# FPGA.net
KiCad netlist of a schematic drawn in Altium Designer
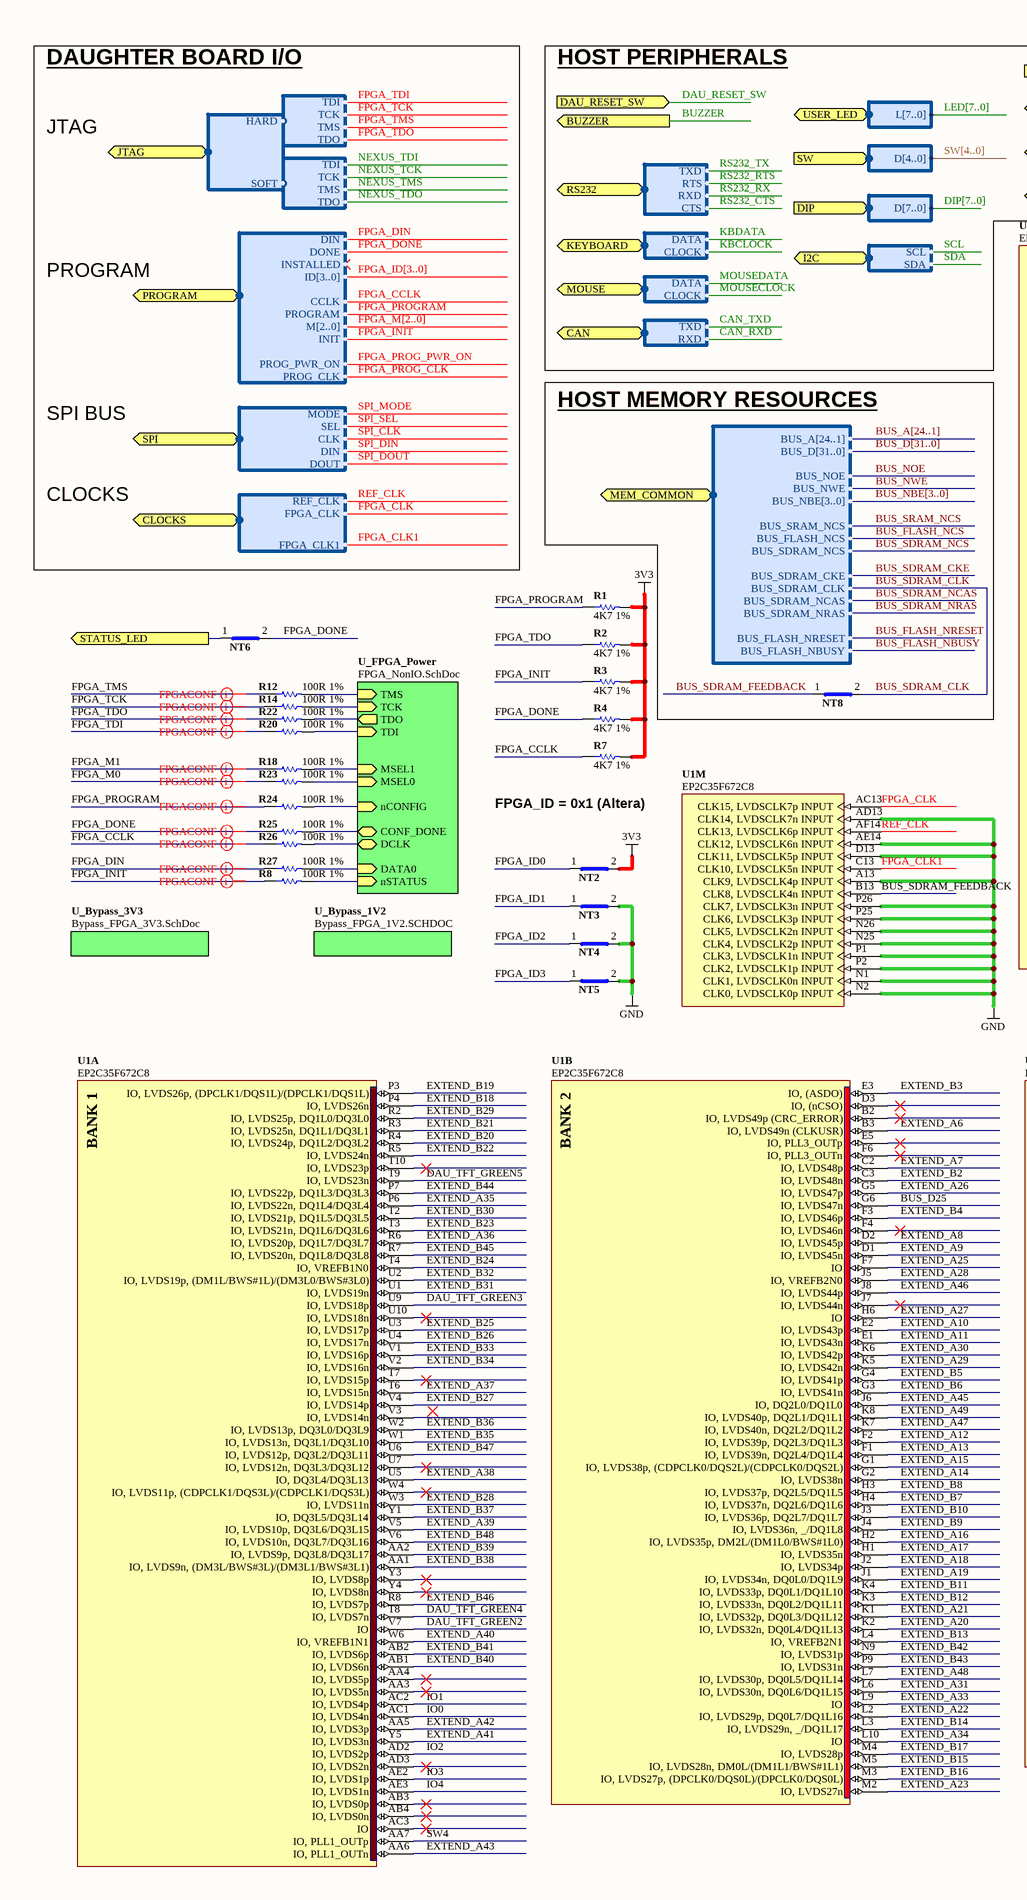
[diagram p0: FPGA.SCHDOC, left]
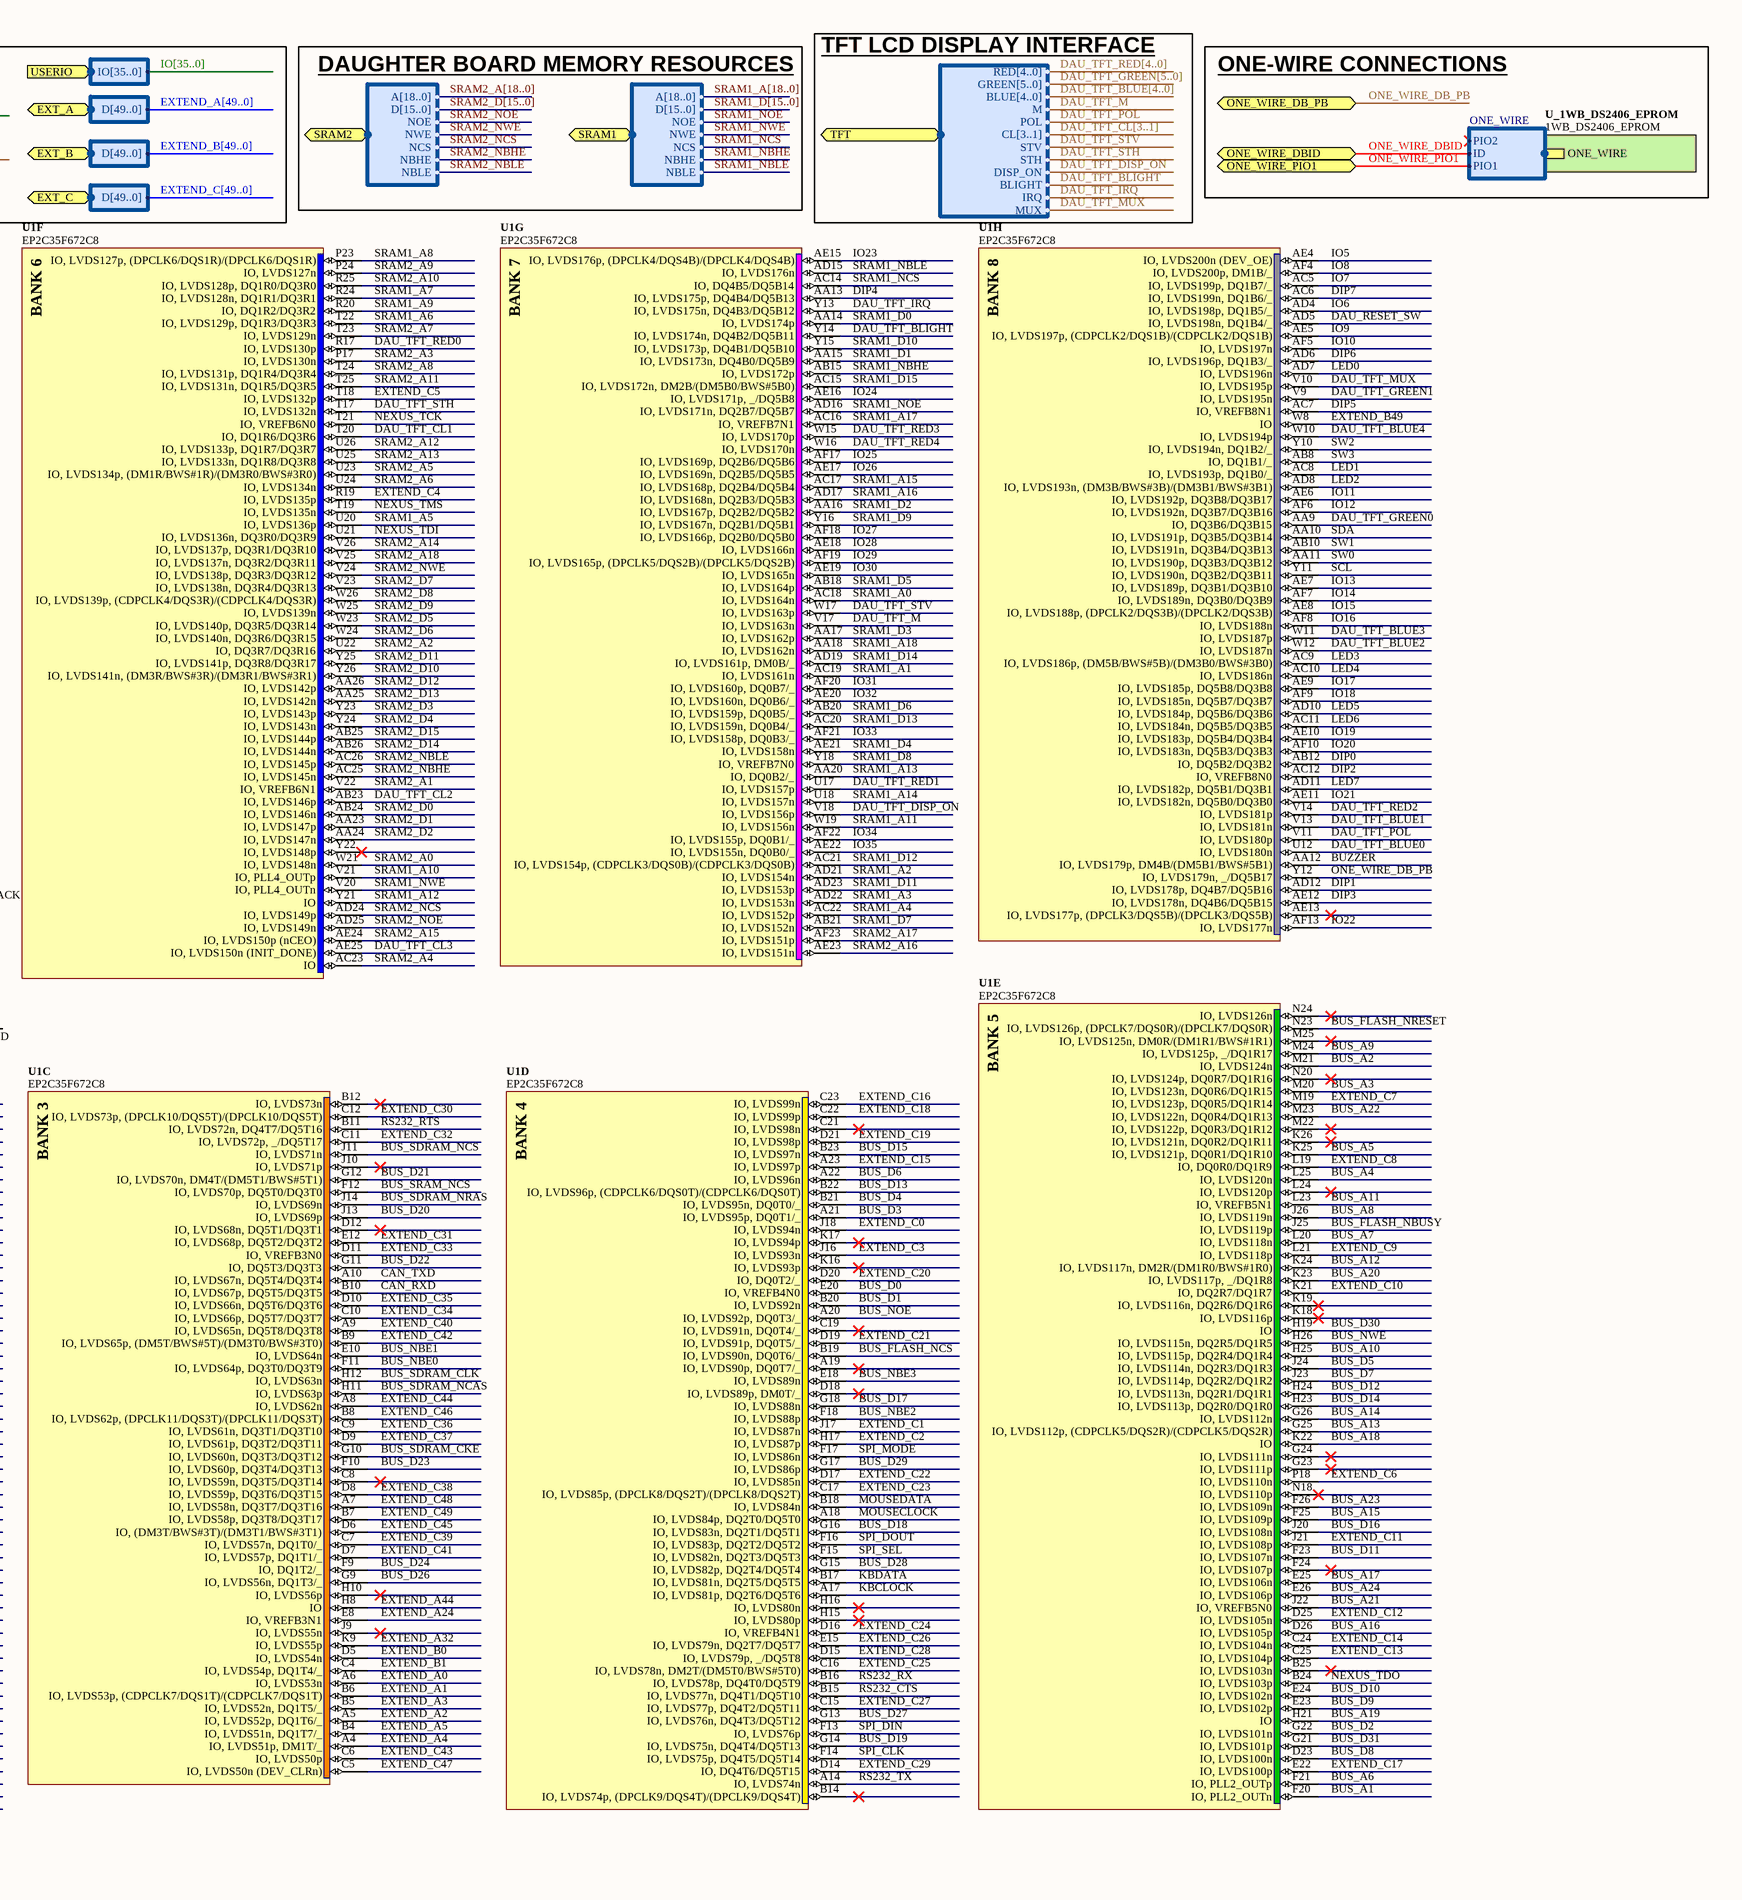
[diagram p1: FPGA.SCHDOC, right]

(export (version "E")
  (design (tool "Eeschema 10.0.6"))
  (components
    (comp (ref "NT2")
      (value "Net Tie SMT2")
      (footprint "NETTIE-SMT2-8X8")
      (description "Net-Tie, Surface Mount, 2 x 0.4mm x 0.2mm SMT Pads - For 0.2mm Track")
      (libsource (lib "AltiumDesignLibrary") (part "NETTIE-SMT2"))
    )
    (comp (ref "NT3")
      (value "Net Tie SMT2")
      (footprint "NETTIE-SMT2-8X8")
      (description "Net-Tie, Surface Mount, 2 x 0.4mm x 0.2mm SMT Pads - For 0.2mm Track")
      (libsource (lib "AltiumDesignLibrary") (part "NETTIE-SMT2"))
    )
    (comp (ref "NT4")
      (value "Net Tie SMT2")
      (footprint "NETTIE-SMT2-8X8")
      (description "Net-Tie, Surface Mount, 2 x 0.4mm x 0.2mm SMT Pads - For 0.2mm Track")
      (libsource (lib "AltiumDesignLibrary") (part "NETTIE-SMT2"))
    )
    (comp (ref "NT5")
      (value "Net Tie SMT2")
      (footprint "NETTIE-SMT2-8X8")
      (description "Net-Tie, Surface Mount, 2 x 0.4mm x 0.2mm SMT Pads - For 0.2mm Track")
      (libsource (lib "AltiumDesignLibrary") (part "NETTIE-SMT2"))
    )
    (comp (ref "NT6")
      (value "Net Tie SMT2")
      (footprint "NETTIE-SMT2-8X8")
      (description "Net-Tie, Surface Mount, 2 x 0.4mm x 0.2mm SMT Pads - For 0.2mm Track")
      (libsource (lib "AltiumDesignLibrary") (part "NETTIE-SMT2"))
    )
    (comp (ref "NT8")
      (value "Net Tie SMT2")
      (footprint "NETTIE-SMT2-8X8")
      (description "Net-Tie, Surface Mount, 2 x 0.4mm x 0.2mm SMT Pads - For 0.2mm Track")
      (libsource (lib "AltiumDesignLibrary") (part "NETTIE-SMT2"))
    )
    (comp (ref "R1")
      (value "4K7 1%")
      (footprint "RESC1005-STAR")
      (description "Resistor, 4K7 1% 0402 (1005)")
      (fields (field (name "TOLERANCE") "1 %"))
      (libsource (lib "AltiumDesignLibrary") (part "RES"))
    )
    (comp (ref "R2")
      (value "4K7 1%")
      (footprint "RESC1005-STAR")
      (description "Resistor, 4K7 1% 0402 (1005)")
      (fields (field (name "TOLERANCE") "1 %"))
      (libsource (lib "AltiumDesignLibrary") (part "RES"))
    )
    (comp (ref "R3")
      (value "4K7 1%")
      (footprint "RESC1005-STAR")
      (description "Resistor, 4K7 1% 0402 (1005)")
      (fields (field (name "TOLERANCE") "1 %"))
      (libsource (lib "AltiumDesignLibrary") (part "RES"))
    )
    (comp (ref "R4")
      (value "4K7 1%")
      (footprint "RESC1005-STAR")
      (description "Resistor, 4K7 1% 0402 (1005)")
      (fields (field (name "TOLERANCE") "1 %"))
      (libsource (lib "AltiumDesignLibrary") (part "RES"))
    )
    (comp (ref "R7")
      (value "4K7 1%")
      (footprint "RESC1005-STAR")
      (description "Resistor, 4K7 1% 0402 (1005)")
      (fields (field (name "TOLERANCE") "1 %"))
      (libsource (lib "AltiumDesignLibrary") (part "RES"))
    )
    (comp (ref "R8")
      (value "100R 1%")
      (footprint "RESC1005-STAR")
      (description "Resistor, 100R 1% 0402 (1005)")
      (fields (field (name "TOLERANCE") "1 %"))
      (libsource (lib "AltiumDesignLibrary") (part "RES"))
    )
    (comp (ref "R12")
      (value "100R 1%")
      (footprint "RESC1005-STAR")
      (description "Resistor, 100R 1% 0402 (1005)")
      (fields (field (name "TOLERANCE") "1 %"))
      (libsource (lib "AltiumDesignLibrary") (part "RES"))
    )
    (comp (ref "R14")
      (value "100R 1%")
      (footprint "RESC1005-STAR")
      (description "Resistor, 100R 1% 0402 (1005)")
      (fields (field (name "TOLERANCE") "1 %"))
      (libsource (lib "AltiumDesignLibrary") (part "RES"))
    )
    (comp (ref "R18")
      (value "100R 1%")
      (footprint "RESC1005-STAR")
      (description "Resistor, 100R 1% 0402 (1005)")
      (fields (field (name "TOLERANCE") "1 %"))
      (libsource (lib "AltiumDesignLibrary") (part "RES"))
    )
    (comp (ref "R20")
      (value "100R 1%")
      (footprint "RESC1005-STAR")
      (description "Resistor, 100R 1% 0402 (1005)")
      (fields (field (name "TOLERANCE") "1 %"))
      (libsource (lib "AltiumDesignLibrary") (part "RES"))
    )
    (comp (ref "R22")
      (value "100R 1%")
      (footprint "RESC1005-STAR")
      (description "Resistor, 100R 1% 0402 (1005)")
      (fields (field (name "TOLERANCE") "1 %"))
      (libsource (lib "AltiumDesignLibrary") (part "RES"))
    )
    (comp (ref "R23")
      (value "100R 1%")
      (footprint "RESC1005-STAR")
      (description "Resistor, 100R 1% 0402 (1005)")
      (fields (field (name "TOLERANCE") "1 %"))
      (libsource (lib "AltiumDesignLibrary") (part "RES"))
    )
    (comp (ref "R24")
      (value "100R 1%")
      (footprint "RESC1005-STAR")
      (description "Resistor, 100R 1% 0402 (1005)")
      (fields (field (name "TOLERANCE") "1 %"))
      (libsource (lib "AltiumDesignLibrary") (part "RES"))
    )
    (comp (ref "R25")
      (value "100R 1%")
      (footprint "RESC1005-STAR")
      (description "Resistor, 100R 1% 0402 (1005)")
      (fields (field (name "TOLERANCE") "1 %"))
      (libsource (lib "AltiumDesignLibrary") (part "RES"))
    )
    (comp (ref "R26")
      (value "100R 1%")
      (footprint "RESC1005-STAR")
      (description "Resistor, 100R 1% 0402 (1005)")
      (fields (field (name "TOLERANCE") "1 %"))
      (libsource (lib "AltiumDesignLibrary") (part "RES"))
    )
    (comp (ref "R27")
      (value "100R 1%")
      (footprint "RESC1005-STAR")
      (description "Resistor, 100R 1% 0402 (1005)")
      (fields (field (name "TOLERANCE") "1 %"))
      (libsource (lib "AltiumDesignLibrary") (part "RES"))
    )
    (comp (ref "U1")
      (value "EP2C35F672C8")
      (footprint "BGA100P26X26-672")
      (description "FPGA, Altera Cyclone2-35 F672")
      (libsource (lib "AltiumDesignLibrary") (part "EP2C35F672C8"))
    )
  )
  (nets
    (net (code "20") (name "/BUS_A1") (class "Default")
      (node (ref "U1") (pin "F20") (pinfunction "IO,_PLL2_OUTn_F20") (pintype "bidirectional"))
    )
    (net (code "21") (name "/BUS_A2") (class "Default")
      (node (ref "U1") (pin "M21") (pinfunction "IO,_LVDS124n_M21") (pintype "bidirectional"))
    )
    (net (code "22") (name "/BUS_A3") (class "Default")
      (node (ref "U1") (pin "M20") (pinfunction "IO,_LVDS123n,_DQ0R6/DQ1R15_M20") (pintype "bidirectional"))
    )
    (net (code "23") (name "/BUS_A4") (class "Default")
      (node (ref "U1") (pin "L25") (pinfunction "IO,_LVDS120n_L25") (pintype "bidirectional"))
    )
    (net (code "24") (name "/BUS_A5") (class "Default")
      (node (ref "U1") (pin "K25") (pinfunction "IO,_LVDS121p,_DQ0R1/DQ1R10_K25") (pintype "bidirectional"))
    )
    (net (code "25") (name "/BUS_A6") (class "Default")
      (node (ref "U1") (pin "F21") (pinfunction "IO,_PLL2_OUTp_F21") (pintype "bidirectional"))
    )
    (net (code "26") (name "/BUS_A7") (class "Default")
      (node (ref "U1") (pin "L20") (pinfunction "IO,_LVDS118n_L20") (pintype "bidirectional"))
    )
    (net (code "27") (name "/BUS_A8") (class "Default")
      (node (ref "U1") (pin "J26") (pinfunction "IO,_LVDS119n_J26") (pintype "bidirectional"))
    )
    (net (code "28") (name "/BUS_A9") (class "Default")
      (node (ref "U1") (pin "M24") (pinfunction "IO,_LVDS125p,__/DQ1R17_M24") (pintype "bidirectional"))
    )
    (net (code "29") (name "/BUS_A10") (class "Default")
      (node (ref "U1") (pin "H25") (pinfunction "IO,_LVDS115p,_DQ2R4/DQ1R4_H25") (pintype "bidirectional"))
    )
    (net (code "30") (name "/BUS_A11") (class "Default")
      (node (ref "U1") (pin "L23") (pinfunction "IO,_VREFB5N1_L23") (pintype "bidirectional"))
    )
    (net (code "31") (name "/BUS_A12") (class "Default")
      (node (ref "U1") (pin "K24") (pinfunction "IO,_LVDS117n,_DM2R/(DM1R0/BWS#1R0)_K24") (pintype "bidirectional"))
    )
    (net (code "32") (name "/BUS_A13") (class "Default")
      (node (ref "U1") (pin "G25") (pinfunction "IO,_LVDS112p,_(CDPCLK5/DQS2R)/(CDPCLK5/DQS2R)_G25") (pintype "bidirectional"))
    )
    (net (code "33") (name "/BUS_A14") (class "Default")
      (node (ref "U1") (pin "G26") (pinfunction "IO,_LVDS112n_G26") (pintype "bidirectional"))
    )
    (net (code "34") (name "/BUS_A15") (class "Default")
      (node (ref "U1") (pin "F25") (pinfunction "IO,_LVDS109p_F25") (pintype "bidirectional"))
    )
    (net (code "35") (name "/BUS_A16") (class "Default")
      (node (ref "U1") (pin "D26") (pinfunction "IO,_LVDS105p_D26") (pintype "bidirectional"))
    )
    (net (code "36") (name "/BUS_A17") (class "Default")
      (node (ref "U1") (pin "E25") (pinfunction "IO,_LVDS106n_E25") (pintype "bidirectional"))
    )
    (net (code "37") (name "/BUS_A18") (class "Default")
      (node (ref "U1") (pin "K22") (pinfunction "IO_K22") (pintype "bidirectional"))
    )
    (net (code "38") (name "/BUS_A19") (class "Default")
      (node (ref "U1") (pin "H21") (pinfunction "IO_H21") (pintype "bidirectional"))
    )
    (net (code "39") (name "/BUS_A20") (class "Default")
      (node (ref "U1") (pin "K23") (pinfunction "IO,_LVDS117p,__/DQ1R8_K23") (pintype "bidirectional"))
    )
    (net (code "40") (name "/BUS_A21") (class "Default")
      (node (ref "U1") (pin "J22") (pinfunction "IO,_VREFB5N0_J22") (pintype "bidirectional"))
    )
    (net (code "41") (name "/BUS_A22") (class "Default")
      (node (ref "U1") (pin "M23") (pinfunction "IO,_LVDS122n,_DQ0R4/DQ1R13_M23") (pintype "bidirectional"))
    )
    (net (code "42") (name "/BUS_A23") (class "Default")
      (node (ref "U1") (pin "F26") (pinfunction "IO,_LVDS109n_F26") (pintype "bidirectional"))
    )
    (net (code "43") (name "/BUS_A24") (class "Default")
      (node (ref "U1") (pin "E26") (pinfunction "IO,_LVDS106p_E26") (pintype "bidirectional"))
    )
    (net (code "44") (name "/BUS_D0") (class "Default")
      (node (ref "U1") (pin "E20") (pinfunction "IO,_VREFB4N0_E20") (pintype "bidirectional"))
    )
    (net (code "45") (name "/BUS_D1") (class "Default")
      (node (ref "U1") (pin "B20") (pinfunction "IO,_LVDS92n_B20") (pintype "bidirectional"))
    )
    (net (code "46") (name "/BUS_D2") (class "Default")
      (node (ref "U1") (pin "G22") (pinfunction "IO,_LVDS101n_G22") (pintype "bidirectional"))
    )
    (net (code "47") (name "/BUS_D3") (class "Default")
      (node (ref "U1") (pin "A21") (pinfunction "IO,_LVDS95p,_DQ0T1/__A21") (pintype "bidirectional"))
    )
    (net (code "48") (name "/BUS_D4") (class "Default")
      (node (ref "U1") (pin "B21") (pinfunction "IO,_LVDS95n,_DQ0T0/__B21") (pintype "bidirectional"))
    )
    (net (code "49") (name "/BUS_D5") (class "Default")
      (node (ref "U1") (pin "J24") (pinfunction "IO,_LVDS114n,_DQ2R3/DQ1R3_J24") (pintype "bidirectional"))
    )
    (net (code "50") (name "/BUS_D6") (class "Default")
      (node (ref "U1") (pin "A22") (pinfunction "IO,_LVDS96n_A22") (pintype "bidirectional"))
    )
    (net (code "51") (name "/BUS_D7") (class "Default")
      (node (ref "U1") (pin "J23") (pinfunction "IO,_LVDS114p,_DQ2R2/DQ1R2_J23") (pintype "bidirectional"))
    )
    (net (code "52") (name "/BUS_D8") (class "Default")
      (node (ref "U1") (pin "D23") (pinfunction "IO,_LVDS100n_D23") (pintype "bidirectional"))
    )
    (net (code "53") (name "/BUS_D9") (class "Default")
      (node (ref "U1") (pin "E23") (pinfunction "IO,_LVDS102p_E23") (pintype "bidirectional"))
    )
    (net (code "54") (name "/BUS_D10") (class "Default")
      (node (ref "U1") (pin "E24") (pinfunction "IO,_LVDS102n_E24") (pintype "bidirectional"))
    )
    (net (code "55") (name "/BUS_D11") (class "Default")
      (node (ref "U1") (pin "F23") (pinfunction "IO,_LVDS107n_F23") (pintype "bidirectional"))
    )
    (net (code "56") (name "/BUS_D12") (class "Default")
      (node (ref "U1") (pin "H24") (pinfunction "IO,_LVDS113n,_DQ2R1/DQ1R1_H24") (pintype "bidirectional"))
    )
    (net (code "57") (name "/BUS_D13") (class "Default")
      (node (ref "U1") (pin "B22") (pinfunction "IO,_LVDS96p,_(CDPCLK6/DQS0T)/(CDPCLK6/DQS0T)_B22") (pintype "bidirectional"))
    )
    (net (code "58") (name "/BUS_D14") (class "Default")
      (node (ref "U1") (pin "H23") (pinfunction "IO,_LVDS113p,_DQ2R0/DQ1R0_H23") (pintype "bidirectional"))
    )
    (net (code "59") (name "/BUS_D15") (class "Default")
      (node (ref "U1") (pin "B23") (pinfunction "IO,_LVDS97n_B23") (pintype "bidirectional"))
    )
    (net (code "60") (name "/BUS_D16") (class "Default")
      (node (ref "U1") (pin "J20") (pinfunction "IO,_LVDS108n_J20") (pintype "bidirectional"))
    )
    (net (code "61") (name "/BUS_D17") (class "Default")
      (node (ref "U1") (pin "G18") (pinfunction "IO,_LVDS88n_G18") (pintype "bidirectional"))
    )
    (net (code "62") (name "/BUS_D18") (class "Default")
      (node (ref "U1") (pin "G16") (pinfunction "IO,_LVDS83n,_DQ2T1/DQ5T1_G16") (pintype "bidirectional"))
    )
    (net (code "63") (name "/BUS_D19") (class "Default")
      (node (ref "U1") (pin "G14") (pinfunction "IO,_LVDS75n,_DQ4T4/DQ5T13_G14") (pintype "bidirectional"))
    )
    (net (code "64") (name "/BUS_D20") (class "Default")
      (node (ref "U1") (pin "J13") (pinfunction "IO,_LVDS69p_J13") (pintype "bidirectional"))
    )
    (net (code "65") (name "/BUS_D21") (class "Default")
      (node (ref "U1") (pin "G12") (pinfunction "IO,_LVDS70n,_DM4T/(DM5T1/BWS#5T1)_G12") (pintype "bidirectional"))
    )
    (net (code "66") (name "/BUS_D22") (class "Default")
      (node (ref "U1") (pin "G11") (pinfunction "IO,_DQ5T3/DQ3T3_G11") (pintype "bidirectional"))
    )
    (net (code "67") (name "/BUS_D23") (class "Default")
      (node (ref "U1") (pin "F10") (pinfunction "IO,_LVDS60p,_DQ3T4/DQ3T13_F10") (pintype "bidirectional"))
    )
    (net (code "68") (name "/BUS_D24") (class "Default")
      (node (ref "U1") (pin "F9") (pinfunction "IO,_DQ1T2/__F9") (pintype "bidirectional"))
    )
    (net (code "69") (name "/BUS_D25") (class "Default")
      (node (ref "U1") (pin "G6") (pinfunction "IO,_LVDS47n_G6") (pintype "bidirectional"))
    )
    (net (code "70") (name "/BUS_D26") (class "Default")
      (node (ref "U1") (pin "G9") (pinfunction "IO,_LVDS56n,_DQ1T3/__G9") (pintype "bidirectional"))
    )
    (net (code "71") (name "/BUS_D27") (class "Default")
      (node (ref "U1") (pin "G13") (pinfunction "IO,_LVDS76n,_DQ4T3/DQ5T12_G13") (pintype "bidirectional"))
    )
    (net (code "72") (name "/BUS_D28") (class "Default")
      (node (ref "U1") (pin "G15") (pinfunction "IO,_LVDS82p,_DQ2T4/DQ5T4_G15") (pintype "bidirectional"))
    )
    (net (code "73") (name "/BUS_D29") (class "Default")
      (node (ref "U1") (pin "G17") (pinfunction "IO,_LVDS86p_G17") (pintype "bidirectional"))
    )
    (net (code "74") (name "/BUS_D30") (class "Default")
      (node (ref "U1") (pin "H19") (pinfunction "IO_H19") (pintype "bidirectional"))
    )
    (net (code "75") (name "/BUS_D31") (class "Default")
      (node (ref "U1") (pin "G21") (pinfunction "IO,_LVDS101p_G21") (pintype "bidirectional"))
    )
    (net (code "77") (name "/BUS_FLASH_NBUSY") (class "Default")
      (node (ref "U1") (pin "J25") (pinfunction "IO,_LVDS119p_J25") (pintype "bidirectional"))
    )
    (net (code "78") (name "/BUS_FLASH_NCS") (class "Default")
      (node (ref "U1") (pin "B19") (pinfunction "IO,_LVDS90n,_DQ0T6/__B19") (pintype "bidirectional"))
    )
    (net (code "79") (name "/BUS_FLASH_NRESET") (class "Default")
      (node (ref "U1") (pin "N23") (pinfunction "IO,_LVDS126p,_(DPCLK7/DQS0R)/(DPCLK7/DQS0R)_N23") (pintype "bidirectional"))
    )
    (net (code "80") (name "/BUS_NBE0") (class "Default")
      (node (ref "U1") (pin "F11") (pinfunction "IO,_LVDS64p,_DQ3T0/DQ3T9_F11") (pintype "bidirectional"))
    )
    (net (code "81") (name "/BUS_NBE1") (class "Default")
      (node (ref "U1") (pin "E10") (pinfunction "IO,_LVDS64n_E10") (pintype "bidirectional"))
    )
    (net (code "82") (name "/BUS_NBE2") (class "Default")
      (node (ref "U1") (pin "F18") (pinfunction "IO,_LVDS88p_F18") (pintype "bidirectional"))
    )
    (net (code "83") (name "/BUS_NBE3") (class "Default")
      (node (ref "U1") (pin "E18") (pinfunction "IO,_LVDS89n_E18") (pintype "bidirectional"))
    )
    (net (code "85") (name "/BUS_NOE") (class "Default")
      (node (ref "U1") (pin "A20") (pinfunction "IO,_LVDS92p,_DQ0T3/__A20") (pintype "bidirectional"))
    )
    (net (code "86") (name "/BUS_NWE") (class "Default")
      (node (ref "U1") (pin "H26") (pinfunction "IO,_LVDS115n,_DQ2R5/DQ1R5_H26") (pintype "bidirectional"))
    )
    (net (code "87") (name "/BUS_SDRAM_CKE") (class "Default")
      (node (ref "U1") (pin "G10") (pinfunction "IO,_LVDS60n,_DQ3T3/DQ3T12_G10") (pintype "bidirectional"))
    )
    (net (code "88") (name "/BUS_SDRAM_CLK") (class "Default")
      (node (ref "NT8") (pin "2") (pinfunction "Net2_2") (pintype "passive"))
      (node (ref "U1") (pin "H12") (pinfunction "IO,_LVDS63n_H12") (pintype "bidirectional"))
    )
    (net (code "89") (name "/BUS_SDRAM_FEEDBACK") (class "Default")
      (node (ref "NT8") (pin "1") (pinfunction "Net1_1") (pintype "passive"))
      (node (ref "U1") (pin "B13") (pinfunction "CLK8,_LVDSCLK4n_INPUT_B13") (pintype "input"))
    )
    (net (code "90") (name "/BUS_SDRAM_NCAS") (class "Default")
      (node (ref "U1") (pin "H11") (pinfunction "IO,_LVDS63p_H11") (pintype "bidirectional"))
    )
    (net (code "91") (name "/BUS_SDRAM_NCS") (class "Default")
      (node (ref "U1") (pin "J11") (pinfunction "IO,_LVDS71n_J11") (pintype "bidirectional"))
    )
    (net (code "92") (name "/BUS_SDRAM_NRAS") (class "Default")
      (node (ref "U1") (pin "J14") (pinfunction "IO,_LVDS69n_J14") (pintype "bidirectional"))
    )
    (net (code "93") (name "/BUS_SRAM_NCS") (class "Default")
      (node (ref "U1") (pin "F12") (pinfunction "IO,_LVDS70p,_DQ5T0/DQ3T0_F12") (pintype "bidirectional"))
    )
    (net (code "94") (name "/BUZZER") (class "Default")
      (node (ref "U1") (pin "AA12") (pinfunction "IO,_LVDS179p,_DM4B/(DM5B1/BWS#5B1)_AA12") (pintype "bidirectional"))
    )
    (net (code "95") (name "/CAN_RXD") (class "Default")
      (node (ref "U1") (pin "B10") (pinfunction "IO,_LVDS67p,_DQ5T5/DQ3T5_B10") (pintype "bidirectional"))
    )
    (net (code "96") (name "/CAN_TXD") (class "Default")
      (node (ref "U1") (pin "A10") (pinfunction "IO,_LVDS67n,_DQ5T4/DQ3T4_A10") (pintype "bidirectional"))
    )
    (net (code "97") (name "/CONF_DONE") (class "Default")
      (node (ref "R25") (pin "2") (pinfunction "2_2") (pintype "passive"))
    )
    (net (code "98") (name "/DATA0") (class "Default")
      (node (ref "R27") (pin "2") (pinfunction "2_2") (pintype "passive"))
    )
    (net (code "99") (name "/DAU_RESET_SW") (class "Default")
      (node (ref "U1") (pin "AD5") (pinfunction "IO,_LVDS198n,_DQ1B4/__AD5") (pintype "bidirectional"))
    )
    (net (code "100") (name "/DAU_TFT_BLIGHT") (class "Default")
      (node (ref "U1") (pin "Y14") (pinfunction "IO,_LVDS174n,_DQ4B2/DQ5B11_Y14") (pintype "bidirectional"))
    )
    (net (code "101") (name "/DAU_TFT_BLUE0") (class "Default")
      (node (ref "U1") (pin "U12") (pinfunction "IO,_LVDS180n_U12") (pintype "bidirectional"))
    )
    (net (code "102") (name "/DAU_TFT_BLUE1") (class "Default")
      (node (ref "U1") (pin "V13") (pinfunction "IO,_LVDS181n_V13") (pintype "bidirectional"))
    )
    (net (code "103") (name "/DAU_TFT_BLUE2") (class "Default")
      (node (ref "U1") (pin "W12") (pinfunction "IO,_LVDS187n_W12") (pintype "bidirectional"))
    )
    (net (code "104") (name "/DAU_TFT_BLUE3") (class "Default")
      (node (ref "U1") (pin "W11") (pinfunction "IO,_LVDS187p_W11") (pintype "bidirectional"))
    )
    (net (code "105") (name "/DAU_TFT_BLUE4") (class "Default")
      (node (ref "U1") (pin "W10") (pinfunction "IO,_LVDS194p_W10") (pintype "bidirectional"))
    )
    (net (code "107") (name "/DAU_TFT_CL1") (class "Default")
      (node (ref "U1") (pin "T20") (pinfunction "IO,_DQ1R6/DQ3R6_T20") (pintype "bidirectional"))
    )
    (net (code "108") (name "/DAU_TFT_CL2") (class "Default")
      (node (ref "U1") (pin "AB23") (pinfunction "IO,_LVDS146p_AB23") (pintype "bidirectional"))
    )
    (net (code "109") (name "/DAU_TFT_CL3") (class "Default")
      (node (ref "U1") (pin "AE25") (pinfunction "IO,_LVDS150n_(INIT_DONE)_AE25") (pintype "bidirectional"))
    )
    (net (code "110") (name "/DAU_TFT_DISP_ON") (class "Default")
      (node (ref "U1") (pin "V18") (pinfunction "IO,_LVDS156p_V18") (pintype "bidirectional"))
    )
    (net (code "111") (name "/DAU_TFT_GREEN0") (class "Default")
      (node (ref "U1") (pin "AA9") (pinfunction "IO,_DQ3B6/DQ3B15_AA9") (pintype "bidirectional"))
    )
    (net (code "112") (name "/DAU_TFT_GREEN1") (class "Default")
      (node (ref "U1") (pin "V9") (pinfunction "IO,_LVDS195n_V9") (pintype "bidirectional"))
    )
    (net (code "113") (name "/DAU_TFT_GREEN2") (class "Default")
      (node (ref "U1") (pin "V7") (pinfunction "IO_V7") (pintype "bidirectional"))
    )
    (net (code "114") (name "/DAU_TFT_GREEN3") (class "Default")
      (node (ref "U1") (pin "U9") (pinfunction "IO,_LVDS18p_U9") (pintype "bidirectional"))
    )
    (net (code "115") (name "/DAU_TFT_GREEN4") (class "Default")
      (node (ref "U1") (pin "T8") (pinfunction "IO,_LVDS7n_T8") (pintype "bidirectional"))
    )
    (net (code "116") (name "/DAU_TFT_GREEN5") (class "Default")
      (node (ref "U1") (pin "T9") (pinfunction "IO,_LVDS23n_T9") (pintype "bidirectional"))
    )
    (net (code "118") (name "/DAU_TFT_IRQ") (class "Default")
      (node (ref "U1") (pin "Y13") (pinfunction "IO,_LVDS175n,_DQ4B3/DQ5B12_Y13") (pintype "bidirectional"))
    )
    (net (code "119") (name "/DAU_TFT_M") (class "Default")
      (node (ref "U1") (pin "V17") (pinfunction "IO,_LVDS163n_V17") (pintype "bidirectional"))
    )
    (net (code "120") (name "/DAU_TFT_MUX") (class "Default")
      (node (ref "U1") (pin "V10") (pinfunction "IO,_LVDS195p_V10") (pintype "bidirectional"))
    )
    (net (code "121") (name "/DAU_TFT_POL") (class "Default")
      (node (ref "U1") (pin "V11") (pinfunction "IO,_LVDS180p_V11") (pintype "bidirectional"))
    )
    (net (code "122") (name "/DAU_TFT_RED0") (class "Default")
      (node (ref "U1") (pin "R17") (pinfunction "IO,_LVDS130p_R17") (pintype "bidirectional"))
    )
    (net (code "123") (name "/DAU_TFT_RED1") (class "Default")
      (node (ref "U1") (pin "U17") (pinfunction "IO,_LVDS157p_U17") (pintype "bidirectional"))
    )
    (net (code "124") (name "/DAU_TFT_RED2") (class "Default")
      (node (ref "U1") (pin "V14") (pinfunction "IO,_LVDS181p_V14") (pintype "bidirectional"))
    )
    (net (code "125") (name "/DAU_TFT_RED3") (class "Default")
      (node (ref "U1") (pin "W15") (pinfunction "IO,_LVDS170p_W15") (pintype "bidirectional"))
    )
    (net (code "126") (name "/DAU_TFT_RED4") (class "Default")
      (node (ref "U1") (pin "W16") (pinfunction "IO,_LVDS170n_W16") (pintype "bidirectional"))
    )
    (net (code "128") (name "/DAU_TFT_STH") (class "Default")
      (node (ref "U1") (pin "T17") (pinfunction "IO,_LVDS132n_T17") (pintype "bidirectional"))
    )
    (net (code "129") (name "/DAU_TFT_STV") (class "Default")
      (node (ref "U1") (pin "W17") (pinfunction "IO,_LVDS163p_W17") (pintype "bidirectional"))
    )
    (net (code "130") (name "/DCLK") (class "Default")
      (node (ref "R26") (pin "2") (pinfunction "2_2") (pintype "passive"))
    )
    (net (code "131") (name "/DIP0") (class "Default")
      (node (ref "U1") (pin "AB12") (pinfunction "IO,_DQ5B2/DQ3B2_AB12") (pintype "bidirectional"))
    )
    (net (code "132") (name "/DIP1") (class "Default")
      (node (ref "U1") (pin "AD12") (pinfunction "IO,_LVDS178p,_DQ4B7/DQ5B16_AD12") (pintype "bidirectional"))
    )
    (net (code "133") (name "/DIP2") (class "Default")
      (node (ref "U1") (pin "AC12") (pinfunction "IO,_VREFB8N0_AC12") (pintype "bidirectional"))
    )
    (net (code "134") (name "/DIP3") (class "Default")
      (node (ref "U1") (pin "AE12") (pinfunction "IO,_LVDS178n,_DQ4B6/DQ5B15_AE12") (pintype "bidirectional"))
    )
    (net (code "135") (name "/DIP4") (class "Default")
      (node (ref "U1") (pin "AA13") (pinfunction "IO,_LVDS175p,_DQ4B4/DQ5B13_AA13") (pintype "bidirectional"))
    )
    (net (code "136") (name "/DIP5") (class "Default")
      (node (ref "U1") (pin "AC7") (pinfunction "IO,_VREFB8N1_AC7") (pintype "bidirectional"))
    )
    (net (code "137") (name "/DIP6") (class "Default")
      (node (ref "U1") (pin "AD6") (pinfunction "IO,_LVDS196p,_DQ1B3/__AD6") (pintype "bidirectional"))
    )
    (net (code "138") (name "/DIP7") (class "Default")
      (node (ref "U1") (pin "AC6") (pinfunction "IO,_LVDS199n,_DQ1B6/__AC6") (pintype "bidirectional"))
    )
    (net (code "140") (name "/EXTEND_A0") (class "Default")
      (node (ref "U1") (pin "A6") (pinfunction "IO,_LVDS53n_A6") (pintype "bidirectional"))
    )
    (net (code "141") (name "/EXTEND_A1") (class "Default")
      (node (ref "U1") (pin "B6") (pinfunction "IO,_LVDS53p,_(CDPCLK7/DQS1T)/(CDPCLK7/DQS1T)_B6") (pintype "bidirectional"))
    )
    (net (code "142") (name "/EXTEND_A2") (class "Default")
      (node (ref "U1") (pin "A5") (pinfunction "IO,_LVDS52p,_DQ1T6/__A5") (pintype "bidirectional"))
    )
    (net (code "143") (name "/EXTEND_A3") (class "Default")
      (node (ref "U1") (pin "B5") (pinfunction "IO,_LVDS52n,_DQ1T5/__B5") (pintype "bidirectional"))
    )
    (net (code "144") (name "/EXTEND_A4") (class "Default")
      (node (ref "U1") (pin "A4") (pinfunction "IO,_LVDS51p,_DM1T/__A4") (pintype "bidirectional"))
    )
    (net (code "145") (name "/EXTEND_A5") (class "Default")
      (node (ref "U1") (pin "B4") (pinfunction "IO,_LVDS51n,_DQ1T7/__B4") (pintype "bidirectional"))
    )
    (net (code "146") (name "/EXTEND_A6") (class "Default")
      (node (ref "U1") (pin "B3") (pinfunction "IO,_LVDS49n_(CLKUSR)_B3") (pintype "bidirectional"))
    )
    (net (code "147") (name "/EXTEND_A7") (class "Default")
      (node (ref "U1") (pin "C2") (pinfunction "IO,_LVDS48p_C2") (pintype "bidirectional"))
    )
    (net (code "148") (name "/EXTEND_A8") (class "Default")
      (node (ref "U1") (pin "D2") (pinfunction "IO,_LVDS45p_D2") (pintype "bidirectional"))
    )
    (net (code "149") (name "/EXTEND_A9") (class "Default")
      (node (ref "U1") (pin "D1") (pinfunction "IO,_LVDS45n_D1") (pintype "bidirectional"))
    )
    (net (code "150") (name "/EXTEND_A10") (class "Default")
      (node (ref "U1") (pin "E2") (pinfunction "IO,_LVDS43p_E2") (pintype "bidirectional"))
    )
    (net (code "151") (name "/EXTEND_A11") (class "Default")
      (node (ref "U1") (pin "E1") (pinfunction "IO,_LVDS43n_E1") (pintype "bidirectional"))
    )
    (net (code "152") (name "/EXTEND_A12") (class "Default")
      (node (ref "U1") (pin "F2") (pinfunction "IO,_LVDS39p,_DQ2L3/DQ1L3_F2") (pintype "bidirectional"))
    )
    (net (code "153") (name "/EXTEND_A13") (class "Default")
      (node (ref "U1") (pin "F1") (pinfunction "IO,_LVDS39n,_DQ2L4/DQ1L4_F1") (pintype "bidirectional"))
    )
    (net (code "154") (name "/EXTEND_A14") (class "Default")
      (node (ref "U1") (pin "G2") (pinfunction "IO,_LVDS38n_G2") (pintype "bidirectional"))
    )
    (net (code "155") (name "/EXTEND_A15") (class "Default")
      (node (ref "U1") (pin "G1") (pinfunction "IO,_LVDS38p,_(CDPCLK0/DQS2L)/(CDPCLK0/DQS2L)_G1") (pintype "bidirectional"))
    )
    (net (code "156") (name "/EXTEND_A16") (class "Default")
      (node (ref "U1") (pin "H2") (pinfunction "IO,_LVDS35p,_DM2L/(DM1L0/BWS#1L0)_H2") (pintype "bidirectional"))
    )
    (net (code "157") (name "/EXTEND_A17") (class "Default")
      (node (ref "U1") (pin "H1") (pinfunction "IO,_LVDS35n_H1") (pintype "bidirectional"))
    )
    (net (code "158") (name "/EXTEND_A18") (class "Default")
      (node (ref "U1") (pin "J2") (pinfunction "IO,_LVDS34p_J2") (pintype "bidirectional"))
    )
    (net (code "159") (name "/EXTEND_A19") (class "Default")
      (node (ref "U1") (pin "J1") (pinfunction "IO,_LVDS34n,_DQ0L0/DQ1L9_J1") (pintype "bidirectional"))
    )
    (net (code "160") (name "/EXTEND_A20") (class "Default")
      (node (ref "U1") (pin "K2") (pinfunction "IO,_LVDS32n,_DQ0L4/DQ1L13_K2") (pintype "bidirectional"))
    )
    (net (code "161") (name "/EXTEND_A21") (class "Default")
      (node (ref "U1") (pin "K1") (pinfunction "IO,_LVDS32p,_DQ0L3/DQ1L12_K1") (pintype "bidirectional"))
    )
    (net (code "162") (name "/EXTEND_A22") (class "Default")
      (node (ref "U1") (pin "L2") (pinfunction "IO,_LVDS29p,_DQ0L7/DQ1L16_L2") (pintype "bidirectional"))
    )
    (net (code "163") (name "/EXTEND_A23") (class "Default")
      (node (ref "U1") (pin "M2") (pinfunction "IO,_LVDS27n_M2") (pintype "bidirectional"))
    )
    (net (code "164") (name "/EXTEND_A24") (class "Default")
      (node (ref "U1") (pin "E8") (pinfunction "IO,_VREFB3N1_E8") (pintype "bidirectional"))
    )
    (net (code "165") (name "/EXTEND_A25") (class "Default")
      (node (ref "U1") (pin "F7") (pinfunction "IO_F7") (pintype "bidirectional"))
    )
    (net (code "166") (name "/EXTEND_A26") (class "Default")
      (node (ref "U1") (pin "G5") (pinfunction "IO,_LVDS47p_G5") (pintype "bidirectional"))
    )
    (net (code "167") (name "/EXTEND_A27") (class "Default")
      (node (ref "U1") (pin "H6") (pinfunction "IO_H6") (pintype "bidirectional"))
    )
    (net (code "168") (name "/EXTEND_A28") (class "Default")
      (node (ref "U1") (pin "J5") (pinfunction "IO,_VREFB2N0_J5") (pintype "bidirectional"))
    )
    (net (code "169") (name "/EXTEND_A29") (class "Default")
      (node (ref "U1") (pin "K5") (pinfunction "IO,_LVDS42n_K5") (pintype "bidirectional"))
    )
    (net (code "170") (name "/EXTEND_A30") (class "Default")
      (node (ref "U1") (pin "K6") (pinfunction "IO,_LVDS42p_K6") (pintype "bidirectional"))
    )
    (net (code "171") (name "/EXTEND_A31") (class "Default")
      (node (ref "U1") (pin "L6") (pinfunction "IO,_LVDS30n,_DQ0L6/DQ1L15_L6") (pintype "bidirectional"))
    )
    (net (code "172") (name "/EXTEND_A32") (class "Default")
      (node (ref "U1") (pin "K9") (pinfunction "IO,_LVDS55p_K9") (pintype "bidirectional"))
    )
    (net (code "173") (name "/EXTEND_A33") (class "Default")
      (node (ref "U1") (pin "L9") (pinfunction "IO_L9") (pintype "bidirectional"))
    )
    (net (code "174") (name "/EXTEND_A34") (class "Default")
      (node (ref "U1") (pin "L10") (pinfunction "IO_L10") (pintype "bidirectional"))
    )
    (net (code "175") (name "/EXTEND_A35") (class "Default")
      (node (ref "U1") (pin "P6") (pinfunction "IO,_LVDS22n,_DQ1L4/DQ3L4_P6") (pintype "bidirectional"))
    )
    (net (code "176") (name "/EXTEND_A36") (class "Default")
      (node (ref "U1") (pin "R6") (pinfunction "IO,_LVDS20p,_DQ1L7/DQ3L7_R6") (pintype "bidirectional"))
    )
    (net (code "177") (name "/EXTEND_A37") (class "Default")
      (node (ref "U1") (pin "T6") (pinfunction "IO,_LVDS15n_T6") (pintype "bidirectional"))
    )
    (net (code "178") (name "/EXTEND_A38") (class "Default")
      (node (ref "U1") (pin "U5") (pinfunction "IO,_DQ3L4/DQ3L13_U5") (pintype "bidirectional"))
    )
    (net (code "179") (name "/EXTEND_A39") (class "Default")
      (node (ref "U1") (pin "V5") (pinfunction "IO,_LVDS10p,_DQ3L6/DQ3L15_V5") (pintype "bidirectional"))
    )
    (net (code "180") (name "/EXTEND_A40") (class "Default")
      (node (ref "U1") (pin "W6") (pinfunction "IO,_VREFB1N1_W6") (pintype "bidirectional"))
    )
    (net (code "181") (name "/EXTEND_A41") (class "Default")
      (node (ref "U1") (pin "Y5") (pinfunction "IO,_LVDS3n_Y5") (pintype "bidirectional"))
    )
    (net (code "182") (name "/EXTEND_A42") (class "Default")
      (node (ref "U1") (pin "AA5") (pinfunction "IO,_LVDS3p_AA5") (pintype "bidirectional"))
    )
    (net (code "183") (name "/EXTEND_A43") (class "Default")
      (node (ref "U1") (pin "AA6") (pinfunction "IO,_PLL1_OUTn_AA6") (pintype "bidirectional"))
    )
    (net (code "184") (name "/EXTEND_A44") (class "Default")
      (node (ref "U1") (pin "H8") (pinfunction "IO_H8") (pintype "bidirectional"))
    )
    (net (code "185") (name "/EXTEND_A45") (class "Default")
      (node (ref "U1") (pin "J6") (pinfunction "IO,_DQ2L0/DQ1L0_J6") (pintype "bidirectional"))
    )
    (net (code "186") (name "/EXTEND_A46") (class "Default")
      (node (ref "U1") (pin "J8") (pinfunction "IO,_LVDS44p_J8") (pintype "bidirectional"))
    )
    (net (code "187") (name "/EXTEND_A47") (class "Default")
      (node (ref "U1") (pin "K7") (pinfunction "IO,_LVDS40n,_DQ2L2/DQ1L2_K7") (pintype "bidirectional"))
    )
    (net (code "188") (name "/EXTEND_A48") (class "Default")
      (node (ref "U1") (pin "L7") (pinfunction "IO,_LVDS30p,_DQ0L5/DQ1L14_L7") (pintype "bidirectional"))
    )
    (net (code "189") (name "/EXTEND_A49") (class "Default")
      (node (ref "U1") (pin "K8") (pinfunction "IO,_LVDS40p,_DQ2L1/DQ1L1_K8") (pintype "bidirectional"))
    )
    (net (code "190") (name "/EXTEND_B0") (class "Default")
      (node (ref "U1") (pin "D5") (pinfunction "IO,_LVDS54n_D5") (pintype "bidirectional"))
    )
    (net (code "191") (name "/EXTEND_B1") (class "Default")
      (node (ref "U1") (pin "C4") (pinfunction "IO,_LVDS54p,_DQ1T4/__C4") (pintype "bidirectional"))
    )
    (net (code "192") (name "/EXTEND_B2") (class "Default")
      (node (ref "U1") (pin "C3") (pinfunction "IO,_LVDS48n_C3") (pintype "bidirectional"))
    )
    (net (code "193") (name "/EXTEND_B3") (class "Default")
      (node (ref "U1") (pin "E3") (pinfunction "IO,_(ASDO)_E3") (pintype "bidirectional"))
    )
    (net (code "194") (name "/EXTEND_B4") (class "Default")
      (node (ref "U1") (pin "F3") (pinfunction "IO,_LVDS46p_F3") (pintype "bidirectional"))
    )
    (net (code "195") (name "/EXTEND_B5") (class "Default")
      (node (ref "U1") (pin "G4") (pinfunction "IO,_LVDS41p_G4") (pintype "bidirectional"))
    )
    (net (code "196") (name "/EXTEND_B6") (class "Default")
      (node (ref "U1") (pin "G3") (pinfunction "IO,_LVDS41n_G3") (pintype "bidirectional"))
    )
    (net (code "197") (name "/EXTEND_B7") (class "Default")
      (node (ref "U1") (pin "H4") (pinfunction "IO,_LVDS37n,_DQ2L6/DQ1L6_H4") (pintype "bidirectional"))
    )
    (net (code "198") (name "/EXTEND_B8") (class "Default")
      (node (ref "U1") (pin "H3") (pinfunction "IO,_LVDS37p,_DQ2L5/DQ1L5_H3") (pintype "bidirectional"))
    )
    (net (code "199") (name "/EXTEND_B9") (class "Default")
      (node (ref "U1") (pin "J4") (pinfunction "IO,_LVDS36n,__/DQ1L8_J4") (pintype "bidirectional"))
    )
    (net (code "200") (name "/EXTEND_B10") (class "Default")
      (node (ref "U1") (pin "J3") (pinfunction "IO,_LVDS36p,_DQ2L7/DQ1L7_J3") (pintype "bidirectional"))
    )
    (net (code "201") (name "/EXTEND_B11") (class "Default")
      (node (ref "U1") (pin "K4") (pinfunction "IO,_LVDS33p,_DQ0L1/DQ1L10_K4") (pintype "bidirectional"))
    )
    (net (code "202") (name "/EXTEND_B12") (class "Default")
      (node (ref "U1") (pin "K3") (pinfunction "IO,_LVDS33n,_DQ0L2/DQ1L11_K3") (pintype "bidirectional"))
    )
    (net (code "203") (name "/EXTEND_B13") (class "Default")
      (node (ref "U1") (pin "L4") (pinfunction "IO,_VREFB2N1_L4") (pintype "bidirectional"))
    )
    (net (code "204") (name "/EXTEND_B14") (class "Default")
      (node (ref "U1") (pin "L3") (pinfunction "IO,_LVDS29n,__/DQ1L17_L3") (pintype "bidirectional"))
    )
    (net (code "205") (name "/EXTEND_B15") (class "Default")
      (node (ref "U1") (pin "M5") (pinfunction "IO,_LVDS28n,_DM0L/(DM1L1/BWS#1L1)_M5") (pintype "bidirectional"))
    )
    (net (code "206") (name "/EXTEND_B16") (class "Default")
      (node (ref "U1") (pin "M3") (pinfunction "IO,_LVDS27p,_(DPCLK0/DQS0L)/(DPCLK0/DQS0L)_M3") (pintype "bidirectional"))
    )
    (net (code "207") (name "/EXTEND_B17") (class "Default")
      (node (ref "U1") (pin "M4") (pinfunction "IO,_LVDS28p_M4") (pintype "bidirectional"))
    )
    (net (code "208") (name "/EXTEND_B18") (class "Default")
      (node (ref "U1") (pin "P4") (pinfunction "IO,_LVDS26n_P4") (pintype "bidirectional"))
    )
    (net (code "209") (name "/EXTEND_B19") (class "Default")
      (node (ref "U1") (pin "P3") (pinfunction "IO,_LVDS26p,_(DPCLK1/DQS1L)/(DPCLK1/DQS1L)_P3") (pintype "bidirectional"))
    )
    (net (code "210") (name "/EXTEND_B20") (class "Default")
      (node (ref "U1") (pin "R4") (pinfunction "IO,_LVDS24p,_DQ1L2/DQ3L2_R4") (pintype "bidirectional"))
    )
    (net (code "211") (name "/EXTEND_B21") (class "Default")
      (node (ref "U1") (pin "R3") (pinfunction "IO,_LVDS25n,_DQ1L1/DQ3L1_R3") (pintype "bidirectional"))
    )
    (net (code "212") (name "/EXTEND_B22") (class "Default")
      (node (ref "U1") (pin "R5") (pinfunction "IO,_LVDS24n_R5") (pintype "bidirectional"))
    )
    (net (code "213") (name "/EXTEND_B23") (class "Default")
      (node (ref "U1") (pin "T3") (pinfunction "IO,_LVDS21n,_DQ1L6/DQ3L6_T3") (pintype "bidirectional"))
    )
    (net (code "214") (name "/EXTEND_B24") (class "Default")
      (node (ref "U1") (pin "T4") (pinfunction "IO,_VREFB1N0_T4") (pintype "bidirectional"))
    )
    (net (code "215") (name "/EXTEND_B25") (class "Default")
      (node (ref "U1") (pin "U3") (pinfunction "IO,_LVDS17p_U3") (pintype "bidirectional"))
    )
    (net (code "216") (name "/EXTEND_B26") (class "Default")
      (node (ref "U1") (pin "U4") (pinfunction "IO,_LVDS17n_U4") (pintype "bidirectional"))
    )
    (net (code "217") (name "/EXTEND_B27") (class "Default")
      (node (ref "U1") (pin "V4") (pinfunction "IO,_LVDS14p_V4") (pintype "bidirectional"))
    )
    (net (code "218") (name "/EXTEND_B28") (class "Default")
      (node (ref "U1") (pin "W3") (pinfunction "IO,_LVDS11n_W3") (pintype "bidirectional"))
    )
    (net (code "219") (name "/EXTEND_B29") (class "Default")
      (node (ref "U1") (pin "R2") (pinfunction "IO,_LVDS25p,_DQ1L0/DQ3L0_R2") (pintype "bidirectional"))
    )
    (net (code "220") (name "/EXTEND_B30") (class "Default")
      (node (ref "U1") (pin "T2") (pinfunction "IO,_LVDS21p,_DQ1L5/DQ3L5_T2") (pintype "bidirectional"))
    )
    (net (code "221") (name "/EXTEND_B31") (class "Default")
      (node (ref "U1") (pin "U1") (pinfunction "IO,_LVDS19n_U1") (pintype "bidirectional"))
    )
    (net (code "222") (name "/EXTEND_B32") (class "Default")
      (node (ref "U1") (pin "U2") (pinfunction "IO,_LVDS19p,_(DM1L/BWS#1L)/(DM3L0/BWS#3L0)_U2") (pintype "bidirectional"))
    )
    (net (code "223") (name "/EXTEND_B33") (class "Default")
      (node (ref "U1") (pin "V1") (pinfunction "IO,_LVDS16p_V1") (pintype "bidirectional"))
    )
    (net (code "224") (name "/EXTEND_B34") (class "Default")
      (node (ref "U1") (pin "V2") (pinfunction "IO,_LVDS16n_V2") (pintype "bidirectional"))
    )
    (net (code "225") (name "/EXTEND_B35") (class "Default")
      (node (ref "U1") (pin "W1") (pinfunction "IO,_LVDS13n,_DQ3L1/DQ3L10_W1") (pintype "bidirectional"))
    )
    (net (code "226") (name "/EXTEND_B36") (class "Default")
      (node (ref "U1") (pin "W2") (pinfunction "IO,_LVDS13p,_DQ3L0/DQ3L9_W2") (pintype "bidirectional"))
    )
    (net (code "227") (name "/EXTEND_B37") (class "Default")
      (node (ref "U1") (pin "Y1") (pinfunction "IO,_DQ3L5/DQ3L14_Y1") (pintype "bidirectional"))
    )
    (net (code "228") (name "/EXTEND_B38") (class "Default")
      (node (ref "U1") (pin "AA1") (pinfunction "IO,_LVDS9n,_(DM3L/BWS#3L)/(DM3L1/BWS#3L1)_AA1") (pintype "bidirectional"))
    )
    (net (code "229") (name "/EXTEND_B39") (class "Default")
      (node (ref "U1") (pin "AA2") (pinfunction "IO,_LVDS9p,_DQ3L8/DQ3L17_AA2") (pintype "bidirectional"))
    )
    (net (code "230") (name "/EXTEND_B40") (class "Default")
      (node (ref "U1") (pin "AB1") (pinfunction "IO,_LVDS6n_AB1") (pintype "bidirectional"))
    )
    (net (code "231") (name "/EXTEND_B41") (class "Default")
      (node (ref "U1") (pin "AB2") (pinfunction "IO,_LVDS6p_AB2") (pintype "bidirectional"))
    )
    (net (code "232") (name "/EXTEND_B42") (class "Default")
      (node (ref "U1") (pin "N9") (pinfunction "IO,_LVDS31p_N9") (pintype "bidirectional"))
    )
    (net (code "233") (name "/EXTEND_B43") (class "Default")
      (node (ref "U1") (pin "P9") (pinfunction "IO,_LVDS31n_P9") (pintype "bidirectional"))
    )
    (net (code "234") (name "/EXTEND_B44") (class "Default")
      (node (ref "U1") (pin "P7") (pinfunction "IO,_LVDS22p,_DQ1L3/DQ3L3_P7") (pintype "bidirectional"))
    )
    (net (code "235") (name "/EXTEND_B45") (class "Default")
      (node (ref "U1") (pin "R7") (pinfunction "IO,_LVDS20n,_DQ1L8/DQ3L8_R7") (pintype "bidirectional"))
    )
    (net (code "236") (name "/EXTEND_B46") (class "Default")
      (node (ref "U1") (pin "R8") (pinfunction "IO,_LVDS7p_R8") (pintype "bidirectional"))
    )
    (net (code "237") (name "/EXTEND_B47") (class "Default")
      (node (ref "U1") (pin "U6") (pinfunction "IO,_LVDS12p,_DQ3L2/DQ3L11_U6") (pintype "bidirectional"))
    )
    (net (code "238") (name "/EXTEND_B48") (class "Default")
      (node (ref "U1") (pin "V6") (pinfunction "IO,_LVDS10n,_DQ3L7/DQ3L16_V6") (pintype "bidirectional"))
    )
    (net (code "239") (name "/EXTEND_B49") (class "Default")
      (node (ref "U1") (pin "W8") (pinfunction "IO_W8") (pintype "bidirectional"))
    )
    (net (code "240") (name "/EXTEND_C0") (class "Default")
      (node (ref "U1") (pin "J18") (pinfunction "IO,_LVDS94n_J18") (pintype "bidirectional"))
    )
    (net (code "241") (name "/EXTEND_C1") (class "Default")
      (node (ref "U1") (pin "J17") (pinfunction "IO,_LVDS87n_J17") (pintype "bidirectional"))
    )
    (net (code "242") (name "/EXTEND_C2") (class "Default")
      (node (ref "U1") (pin "H17") (pinfunction "IO,_LVDS87p_H17") (pintype "bidirectional"))
    )
    (net (code "243") (name "/EXTEND_C3") (class "Default")
      (node (ref "U1") (pin "J16") (pinfunction "IO,_LVDS93n_J16") (pintype "bidirectional"))
    )
    (net (code "244") (name "/EXTEND_C4") (class "Default")
      (node (ref "U1") (pin "R19") (pinfunction "IO,_LVDS135p_R19") (pintype "bidirectional"))
    )
    (net (code "245") (name "/EXTEND_C5") (class "Default")
      (node (ref "U1") (pin "T18") (pinfunction "IO,_LVDS132p_T18") (pintype "bidirectional"))
    )
    (net (code "246") (name "/EXTEND_C6") (class "Default")
      (node (ref "U1") (pin "P18") (pinfunction "IO,_LVDS110n_P18") (pintype "bidirectional"))
    )
    (net (code "247") (name "/EXTEND_C7") (class "Default")
      (node (ref "U1") (pin "M19") (pinfunction "IO,_LVDS123p,_DQ0R5/DQ1R14_M19") (pintype "bidirectional"))
    )
    (net (code "248") (name "/EXTEND_C8") (class "Default")
      (node (ref "U1") (pin "L19") (pinfunction "IO,_DQ0R0/DQ1R9_L19") (pintype "bidirectional"))
    )
    (net (code "249") (name "/EXTEND_C9") (class "Default")
      (node (ref "U1") (pin "L21") (pinfunction "IO,_LVDS118p_L21") (pintype "bidirectional"))
    )
    (net (code "250") (name "/EXTEND_C10") (class "Default")
      (node (ref "U1") (pin "K21") (pinfunction "IO,_DQ2R7/DQ1R7_K21") (pintype "bidirectional"))
    )
    (net (code "251") (name "/EXTEND_C11") (class "Default")
      (node (ref "U1") (pin "J21") (pinfunction "IO,_LVDS108p_J21") (pintype "bidirectional"))
    )
    (net (code "252") (name "/EXTEND_C12") (class "Default")
      (node (ref "U1") (pin "D25") (pinfunction "IO,_LVDS105n_D25") (pintype "bidirectional"))
    )
    (net (code "253") (name "/EXTEND_C13") (class "Default")
      (node (ref "U1") (pin "C25") (pinfunction "IO,_LVDS104p_C25") (pintype "bidirectional"))
    )
    (net (code "254") (name "/EXTEND_C14") (class "Default")
      (node (ref "U1") (pin "C24") (pinfunction "IO,_LVDS104n_C24") (pintype "bidirectional"))
    )
    (net (code "255") (name "/EXTEND_C15") (class "Default")
      (node (ref "U1") (pin "A23") (pinfunction "IO,_LVDS97p_A23") (pintype "bidirectional"))
    )
    (net (code "256") (name "/EXTEND_C16") (class "Default")
      (node (ref "U1") (pin "C23") (pinfunction "IO,_LVDS99n_C23") (pintype "bidirectional"))
    )
    (net (code "257") (name "/EXTEND_C17") (class "Default")
      (node (ref "U1") (pin "E22") (pinfunction "IO,_LVDS100p_E22") (pintype "bidirectional"))
    )
    (net (code "258") (name "/EXTEND_C18") (class "Default")
      (node (ref "U1") (pin "C22") (pinfunction "IO,_LVDS99p_C22") (pintype "bidirectional"))
    )
    (net (code "259") (name "/EXTEND_C19") (class "Default")
      (node (ref "U1") (pin "D21") (pinfunction "IO,_LVDS98p_D21") (pintype "bidirectional"))
    )
    (net (code "260") (name "/EXTEND_C20") (class "Default")
      (node (ref "U1") (pin "D20") (pinfunction "IO,_DQ0T2/__D20") (pintype "bidirectional"))
    )
    (net (code "261") (name "/EXTEND_C21") (class "Default")
      (node (ref "U1") (pin "D19") (pinfunction "IO,_LVDS91p,_DQ0T5/__D19") (pintype "bidirectional"))
    )
    (net (code "262") (name "/EXTEND_C22") (class "Default")
      (node (ref "U1") (pin "D17") (pinfunction "IO,_LVDS85n_D17") (pintype "bidirectional"))
    )
    (net (code "263") (name "/EXTEND_C23") (class "Default")
      (node (ref "U1") (pin "C17") (pinfunction "IO,_LVDS85p,_(DPCLK8/DQS2T)/(DPCLK8/DQS2T)_C17") (pintype "bidirectional"))
    )
    (net (code "264") (name "/EXTEND_C24") (class "Default")
      (node (ref "U1") (pin "D16") (pinfunction "IO,_VREFB4N1_D16") (pintype "bidirectional"))
    )
    (net (code "265") (name "/EXTEND_C25") (class "Default")
      (node (ref "U1") (pin "C16") (pinfunction "IO,_LVDS78n,_DM2T/(DM5T0/BWS#5T0)_C16") (pintype "bidirectional"))
    )
    (net (code "266") (name "/EXTEND_C26") (class "Default")
      (node (ref "U1") (pin "E15") (pinfunction "IO,_LVDS79n,_DQ2T7/DQ5T7_E15") (pintype "bidirectional"))
    )
    (net (code "267") (name "/EXTEND_C27") (class "Default")
      (node (ref "U1") (pin "C15") (pinfunction "IO,_LVDS77p,_DQ4T2/DQ5T11_C15") (pintype "bidirectional"))
    )
    (net (code "268") (name "/EXTEND_C28") (class "Default")
      (node (ref "U1") (pin "D15") (pinfunction "IO,_LVDS79p,__/DQ5T8_D15") (pintype "bidirectional"))
    )
    (net (code "269") (name "/EXTEND_C29") (class "Default")
      (node (ref "U1") (pin "D14") (pinfunction "IO,_DQ4T6/DQ5T15_D14") (pintype "bidirectional"))
    )
    (net (code "270") (name "/EXTEND_C30") (class "Default")
      (node (ref "U1") (pin "C12") (pinfunction "IO,_LVDS73p,_(DPCLK10/DQS5T)/(DPCLK10/DQS5T)_C12") (pintype "bidirectional"))
    )
    (net (code "271") (name "/EXTEND_C31") (class "Default")
      (node (ref "U1") (pin "E12") (pinfunction "IO,_LVDS68p,_DQ5T2/DQ3T2_E12") (pintype "bidirectional"))
    )
    (net (code "272") (name "/EXTEND_C32") (class "Default")
      (node (ref "U1") (pin "C11") (pinfunction "IO,_LVDS72p,__/DQ5T17_C11") (pintype "bidirectional"))
    )
    (net (code "273") (name "/EXTEND_C33") (class "Default")
      (node (ref "U1") (pin "D11") (pinfunction "IO,_VREFB3N0_D11") (pintype "bidirectional"))
    )
    (net (code "274") (name "/EXTEND_C34") (class "Default")
      (node (ref "U1") (pin "C10") (pinfunction "IO,_LVDS66p,_DQ5T7/DQ3T7_C10") (pintype "bidirectional"))
    )
    (net (code "275") (name "/EXTEND_C35") (class "Default")
      (node (ref "U1") (pin "D10") (pinfunction "IO,_LVDS66n,_DQ5T6/DQ3T6_D10") (pintype "bidirectional"))
    )
    (net (code "276") (name "/EXTEND_C36") (class "Default")
      (node (ref "U1") (pin "C9") (pinfunction "IO,_LVDS61n,_DQ3T1/DQ3T10_C9") (pintype "bidirectional"))
    )
    (net (code "277") (name "/EXTEND_C37") (class "Default")
      (node (ref "U1") (pin "D9") (pinfunction "IO,_LVDS61p,_DQ3T2/DQ3T11_D9") (pintype "bidirectional"))
    )
    (net (code "278") (name "/EXTEND_C38") (class "Default")
      (node (ref "U1") (pin "D8") (pinfunction "IO,_LVDS59p,_DQ3T6/DQ3T15_D8") (pintype "bidirectional"))
    )
    (net (code "279") (name "/EXTEND_C39") (class "Default")
      (node (ref "U1") (pin "C7") (pinfunction "IO,_LVDS57n,_DQ1T0/__C7") (pintype "bidirectional"))
    )
    (net (code "280") (name "/EXTEND_C40") (class "Default")
      (node (ref "U1") (pin "A9") (pinfunction "IO,_LVDS65n,_DQ5T8/DQ3T8_A9") (pintype "bidirectional"))
    )
    (net (code "281") (name "/EXTEND_C41") (class "Default")
      (node (ref "U1") (pin "D7") (pinfunction "IO,_LVDS57p,_DQ1T1/__D7") (pintype "bidirectional"))
    )
    (net (code "282") (name "/EXTEND_C42") (class "Default")
      (node (ref "U1") (pin "B9") (pinfunction "IO,_LVDS65p,_(DM5T/BWS#5T)/(DM3T0/BWS#3T0)_B9") (pintype "bidirectional"))
    )
    (net (code "283") (name "/EXTEND_C43") (class "Default")
      (node (ref "U1") (pin "C6") (pinfunction "IO,_LVDS50p_C6") (pintype "bidirectional"))
    )
    (net (code "284") (name "/EXTEND_C44") (class "Default")
      (node (ref "U1") (pin "A8") (pinfunction "IO,_LVDS62n_A8") (pintype "bidirectional"))
    )
    (net (code "285") (name "/EXTEND_C45") (class "Default")
      (node (ref "U1") (pin "D6") (pinfunction "IO,_(DM3T/BWS#3T)/(DM3T1/BWS#3T1)_D6") (pintype "bidirectional"))
    )
    (net (code "286") (name "/EXTEND_C46") (class "Default")
      (node (ref "U1") (pin "B8") (pinfunction "IO,_LVDS62p,_(DPCLK11/DQS3T)/(DPCLK11/DQS3T)_B8") (pintype "bidirectional"))
    )
    (net (code "287") (name "/EXTEND_C47") (class "Default")
      (node (ref "U1") (pin "C5") (pinfunction "IO,_LVDS50n_(DEV_CLRn)_C5") (pintype "bidirectional"))
    )
    (net (code "288") (name "/EXTEND_C48") (class "Default")
      (node (ref "U1") (pin "A7") (pinfunction "IO,_LVDS58n,_DQ3T7/DQ3T16_A7") (pintype "bidirectional"))
    )
    (net (code "289") (name "/EXTEND_C49") (class "Default")
      (node (ref "U1") (pin "B7") (pinfunction "IO,_LVDS58p,_DQ3T8/DQ3T17_B7") (pintype "bidirectional"))
    )
    (net (code "293") (name "/FPGA_CCLK") (class "Default")
      (node (ref "R26") (pin "1") (pinfunction "1_1") (pintype "passive"))
      (node (ref "R7") (pin "1") (pinfunction "1_1") (pintype "passive"))
    )
    (net (code "294") (name "/FPGA_CLK") (class "Default")
      (node (ref "U1") (pin "AC13") (pinfunction "CLK15,_LVDSCLK7p_INPUT_AC13") (pintype "input"))
    )
    (net (code "295") (name "/FPGA_CLK1") (class "Default")
      (node (ref "U1") (pin "C13") (pinfunction "CLK10,_LVDSCLK5n_INPUT_C13") (pintype "input"))
    )
    (net (code "296") (name "/FPGA_DIN") (class "Default")
      (node (ref "R27") (pin "1") (pinfunction "1_1") (pintype "passive"))
    )
    (net (code "297") (name "/FPGA_DONE") (class "Default")
      (node (ref "NT6") (pin "2") (pinfunction "Net2_2") (pintype "passive"))
      (node (ref "R25") (pin "1") (pinfunction "1_1") (pintype "passive"))
      (node (ref "R4") (pin "1") (pinfunction "1_1") (pintype "passive"))
    )
    (net (code "298") (name "/FPGA_ID0") (class "Default")
      (node (ref "NT2") (pin "1") (pinfunction "Net1_1") (pintype "passive"))
    )
    (net (code "299") (name "/FPGA_ID1") (class "Default")
      (node (ref "NT3") (pin "1") (pinfunction "Net1_1") (pintype "passive"))
    )
    (net (code "300") (name "/FPGA_ID2") (class "Default")
      (node (ref "NT4") (pin "1") (pinfunction "Net1_1") (pintype "passive"))
    )
    (net (code "301") (name "/FPGA_ID3") (class "Default")
      (node (ref "NT5") (pin "1") (pinfunction "Net1_1") (pintype "passive"))
    )
    (net (code "303") (name "/FPGA_INIT") (class "Default")
      (node (ref "R3") (pin "1") (pinfunction "1_1") (pintype "passive"))
      (node (ref "R8") (pin "1") (pinfunction "1_1") (pintype "passive"))
    )
    (net (code "304") (name "/FPGA_M0") (class "Default")
      (node (ref "R23") (pin "1") (pinfunction "1_1") (pintype "passive"))
    )
    (net (code "305") (name "/FPGA_M1") (class "Default")
      (node (ref "R18") (pin "1") (pinfunction "1_1") (pintype "passive"))
    )
    (net (code "306") (name "/FPGA_PROGRAM") (class "Default")
      (node (ref "R1") (pin "1") (pinfunction "1_1") (pintype "passive"))
      (node (ref "R24") (pin "1") (pinfunction "1_1") (pintype "passive"))
    )
    (net (code "309") (name "/FPGA_TCK") (class "Default")
      (node (ref "R14") (pin "1") (pinfunction "1_1") (pintype "passive"))
    )
    (net (code "310") (name "/FPGA_TDI") (class "Default")
      (node (ref "R20") (pin "1") (pinfunction "1_1") (pintype "passive"))
    )
    (net (code "311") (name "/FPGA_TDO") (class "Default")
      (node (ref "R2") (pin "1") (pinfunction "1_1") (pintype "passive"))
      (node (ref "R22") (pin "1") (pinfunction "1_1") (pintype "passive"))
    )
    (net (code "312") (name "/FPGA_TMS") (class "Default")
      (node (ref "R12") (pin "1") (pinfunction "1_1") (pintype "passive"))
    )
    (net (code "313") (name "/IO0") (class "Default")
      (node (ref "U1") (pin "AC1") (pinfunction "IO,_LVDS4n_AC1") (pintype "bidirectional"))
    )
    (net (code "314") (name "/IO1") (class "Default")
      (node (ref "U1") (pin "AC2") (pinfunction "IO,_LVDS4p_AC2") (pintype "bidirectional"))
    )
    (net (code "315") (name "/IO2") (class "Default")
      (node (ref "U1") (pin "AD2") (pinfunction "IO,_LVDS2p_AD2") (pintype "bidirectional"))
    )
    (net (code "316") (name "/IO3") (class "Default")
      (node (ref "U1") (pin "AE2") (pinfunction "IO,_LVDS1p_AE2") (pintype "bidirectional"))
    )
    (net (code "317") (name "/IO4") (class "Default")
      (node (ref "U1") (pin "AE3") (pinfunction "IO,_LVDS1n_AE3") (pintype "bidirectional"))
    )
    (net (code "318") (name "/IO5") (class "Default")
      (node (ref "U1") (pin "AE4") (pinfunction "IO,_LVDS200n_(DEV_OE)_AE4") (pintype "bidirectional"))
    )
    (net (code "319") (name "/IO6") (class "Default")
      (node (ref "U1") (pin "AD4") (pinfunction "IO,_LVDS198p,_DQ1B5/__AD4") (pintype "bidirectional"))
    )
    (net (code "320") (name "/IO7") (class "Default")
      (node (ref "U1") (pin "AC5") (pinfunction "IO,_LVDS199p,_DQ1B7/__AC5") (pintype "bidirectional"))
    )
    (net (code "321") (name "/IO8") (class "Default")
      (node (ref "U1") (pin "AF4") (pinfunction "IO,_LVDS200p,_DM1B/__AF4") (pintype "bidirectional"))
    )
    (net (code "322") (name "/IO9") (class "Default")
      (node (ref "U1") (pin "AE5") (pinfunction "IO,_LVDS197p,_(CDPCLK2/DQS1B)/(CDPCLK2/DQS1B)_AE5") (pintype "bidirectional"))
    )
    (net (code "323") (name "/IO10") (class "Default")
      (node (ref "U1") (pin "AF5") (pinfunction "IO,_LVDS197n_AF5") (pintype "bidirectional"))
    )
    (net (code "324") (name "/IO11") (class "Default")
      (node (ref "U1") (pin "AE6") (pinfunction "IO,_LVDS192p,_DQ3B8/DQ3B17_AE6") (pintype "bidirectional"))
    )
    (net (code "325") (name "/IO12") (class "Default")
      (node (ref "U1") (pin "AF6") (pinfunction "IO,_LVDS192n,_DQ3B7/DQ3B16_AF6") (pintype "bidirectional"))
    )
    (net (code "326") (name "/IO13") (class "Default")
      (node (ref "U1") (pin "AE7") (pinfunction "IO,_LVDS189p,_DQ3B1/DQ3B10_AE7") (pintype "bidirectional"))
    )
    (net (code "327") (name "/IO14") (class "Default")
      (node (ref "U1") (pin "AF7") (pinfunction "IO,_LVDS189n,_DQ3B0/DQ3B9_AF7") (pintype "bidirectional"))
    )
    (net (code "328") (name "/IO15") (class "Default")
      (node (ref "U1") (pin "AE8") (pinfunction "IO,_LVDS188p,_(DPCLK2/DQS3B)/(DPCLK2/DQS3B)_AE8") (pintype "bidirectional"))
    )
    (net (code "329") (name "/IO16") (class "Default")
      (node (ref "U1") (pin "AF8") (pinfunction "IO,_LVDS188n_AF8") (pintype "bidirectional"))
    )
    (net (code "330") (name "/IO17") (class "Default")
      (node (ref "U1") (pin "AE9") (pinfunction "IO,_LVDS185p,_DQ5B8/DQ3B8_AE9") (pintype "bidirectional"))
    )
    (net (code "331") (name "/IO18") (class "Default")
      (node (ref "U1") (pin "AF9") (pinfunction "IO,_LVDS185n,_DQ5B7/DQ3B7_AF9") (pintype "bidirectional"))
    )
    (net (code "332") (name "/IO19") (class "Default")
      (node (ref "U1") (pin "AE10") (pinfunction "IO,_LVDS183p,_DQ5B4/DQ3B4_AE10") (pintype "bidirectional"))
    )
    (net (code "333") (name "/IO20") (class "Default")
      (node (ref "U1") (pin "AF10") (pinfunction "IO,_LVDS183n,_DQ5B3/DQ3B3_AF10") (pintype "bidirectional"))
    )
    (net (code "334") (name "/IO21") (class "Default")
      (node (ref "U1") (pin "AE11") (pinfunction "IO,_LVDS182n,_DQ5B0/DQ3B0_AE11") (pintype "bidirectional"))
    )
    (net (code "335") (name "/IO22") (class "Default")
      (node (ref "U1") (pin "AF13") (pinfunction "IO,_LVDS177n_AF13") (pintype "bidirectional"))
    )
    (net (code "336") (name "/IO23") (class "Default")
      (node (ref "U1") (pin "AE15") (pinfunction "IO,_LVDS176p,_(DPCLK4/DQS4B)/(DPCLK4/DQS4B)_AE15") (pintype "bidirectional"))
    )
    (net (code "337") (name "/IO24") (class "Default")
      (node (ref "U1") (pin "AE16") (pinfunction "IO,_LVDS171p,__/DQ5B8_AE16") (pintype "bidirectional"))
    )
    (net (code "338") (name "/IO25") (class "Default")
      (node (ref "U1") (pin "AF17") (pinfunction "IO,_LVDS169p,_DQ2B6/DQ5B6_AF17") (pintype "bidirectional"))
    )
    (net (code "339") (name "/IO26") (class "Default")
      (node (ref "U1") (pin "AE17") (pinfunction "IO,_LVDS169n,_DQ2B5/DQ5B5_AE17") (pintype "bidirectional"))
    )
    (net (code "340") (name "/IO27") (class "Default")
      (node (ref "U1") (pin "AF18") (pinfunction "IO,_LVDS166p,_DQ2B0/DQ5B0_AF18") (pintype "bidirectional"))
    )
    (net (code "341") (name "/IO28") (class "Default")
      (node (ref "U1") (pin "AE18") (pinfunction "IO,_LVDS166n_AE18") (pintype "bidirectional"))
    )
    (net (code "342") (name "/IO29") (class "Default")
      (node (ref "U1") (pin "AF19") (pinfunction "IO,_LVDS165p,_(DPCLK5/DQS2B)/(DPCLK5/DQS2B)_AF19") (pintype "bidirectional"))
    )
    (net (code "343") (name "/IO30") (class "Default")
      (node (ref "U1") (pin "AE19") (pinfunction "IO,_LVDS165n_AE19") (pintype "bidirectional"))
    )
    (net (code "344") (name "/IO31") (class "Default")
      (node (ref "U1") (pin "AF20") (pinfunction "IO,_LVDS160p,_DQ0B7/__AF20") (pintype "bidirectional"))
    )
    (net (code "345") (name "/IO32") (class "Default")
      (node (ref "U1") (pin "AE20") (pinfunction "IO,_LVDS160n,_DQ0B6/__AE20") (pintype "bidirectional"))
    )
    (net (code "346") (name "/IO33") (class "Default")
      (node (ref "U1") (pin "AF21") (pinfunction "IO,_LVDS158p,_DQ0B3/__AF21") (pintype "bidirectional"))
    )
    (net (code "347") (name "/IO34") (class "Default")
      (node (ref "U1") (pin "AF22") (pinfunction "IO,_LVDS155p,_DQ0B1/__AF22") (pintype "bidirectional"))
    )
    (net (code "348") (name "/IO35") (class "Default")
      (node (ref "U1") (pin "AE22") (pinfunction "IO,_LVDS155n,_DQ0B0/__AE22") (pintype "bidirectional"))
    )
    (net (code "349") (name "/KBCLOCK") (class "Default")
      (node (ref "U1") (pin "A17") (pinfunction "IO,_LVDS81p,_DQ2T6/DQ5T6_A17") (pintype "bidirectional"))
    )
    (net (code "350") (name "/KBDATA") (class "Default")
      (node (ref "U1") (pin "B17") (pinfunction "IO,_LVDS81n,_DQ2T5/DQ5T5_B17") (pintype "bidirectional"))
    )
    (net (code "351") (name "/LED0") (class "Default")
      (node (ref "U1") (pin "AD7") (pinfunction "IO,_LVDS196n_AD7") (pintype "bidirectional"))
    )
    (net (code "352") (name "/LED1") (class "Default")
      (node (ref "U1") (pin "AC8") (pinfunction "IO,_LVDS193p,_DQ1B0/__AC8") (pintype "bidirectional"))
    )
    (net (code "353") (name "/LED2") (class "Default")
      (node (ref "U1") (pin "AD8") (pinfunction "IO,_LVDS193n,_(DM3B/BWS#3B)/(DM3B1/BWS#3B1)_AD8") (pintype "bidirectional"))
    )
    (net (code "354") (name "/LED3") (class "Default")
      (node (ref "U1") (pin "AC9") (pinfunction "IO,_LVDS186p,_(DM5B/BWS#5B)/(DM3B0/BWS#3B0)_AC9") (pintype "bidirectional"))
    )
    (net (code "355") (name "/LED4") (class "Default")
      (node (ref "U1") (pin "AC10") (pinfunction "IO,_LVDS186n_AC10") (pintype "bidirectional"))
    )
    (net (code "356") (name "/LED5") (class "Default")
      (node (ref "U1") (pin "AD10") (pinfunction "IO,_LVDS184p,_DQ5B6/DQ3B6_AD10") (pintype "bidirectional"))
    )
    (net (code "357") (name "/LED6") (class "Default")
      (node (ref "U1") (pin "AC11") (pinfunction "IO,_LVDS184n,_DQ5B5/DQ3B5_AC11") (pintype "bidirectional"))
    )
    (net (code "358") (name "/LED7") (class "Default")
      (node (ref "U1") (pin "AD11") (pinfunction "IO,_LVDS182p,_DQ5B1/DQ3B1_AD11") (pintype "bidirectional"))
    )
    (net (code "360") (name "/MOUSECLOCK") (class "Default")
      (node (ref "U1") (pin "A18") (pinfunction "IO,_LVDS84p,_DQ2T0/DQ5T0_A18") (pintype "bidirectional"))
    )
    (net (code "361") (name "/MOUSEDATA") (class "Default")
      (node (ref "U1") (pin "B18") (pinfunction "IO,_LVDS84n_B18") (pintype "bidirectional"))
    )
    (net (code "362") (name "/MSEL0") (class "Default")
      (node (ref "R23") (pin "2") (pinfunction "2_2") (pintype "passive"))
    )
    (net (code "363") (name "/MSEL1") (class "Default")
      (node (ref "R18") (pin "2") (pinfunction "2_2") (pintype "passive"))
    )
    (net (code "364") (name "/NEXUS_TCK") (class "Default")
      (node (ref "U1") (pin "T21") (pinfunction "IO,_VREFB6N0_T21") (pintype "bidirectional"))
    )
    (net (code "365") (name "/NEXUS_TDI") (class "Default")
      (node (ref "U1") (pin "U21") (pinfunction "IO,_LVDS136n,_DQ3R0/DQ3R9_U21") (pintype "bidirectional"))
    )
    (net (code "366") (name "/NEXUS_TDO") (class "Default")
      (node (ref "U1") (pin "B24") (pinfunction "IO,_LVDS103p_B24") (pintype "bidirectional"))
    )
    (net (code "367") (name "/NEXUS_TMS") (class "Default")
      (node (ref "U1") (pin "T19") (pinfunction "IO,_LVDS135n_T19") (pintype "bidirectional"))
    )
    (net (code "369") (name "/ONE_WIRE_DB_PB") (class "Default")
      (node (ref "U1") (pin "Y12") (pinfunction "IO,_LVDS179n,__/DQ5B17_Y12") (pintype "bidirectional"))
    )
    (net (code "373") (name "/REF_CLK") (class "Default")
      (node (ref "U1") (pin "AF14") (pinfunction "CLK13,_LVDSCLK6p_INPUT_AF14") (pintype "input"))
    )
    (net (code "374") (name "/RS232_CTS") (class "Default")
      (node (ref "U1") (pin "B15") (pinfunction "IO,_LVDS77n,_DQ4T1/DQ5T10_B15") (pintype "bidirectional"))
    )
    (net (code "375") (name "/RS232_RTS") (class "Default")
      (node (ref "U1") (pin "B11") (pinfunction "IO,_LVDS72n,_DQ4T7/DQ5T16_B11") (pintype "bidirectional"))
    )
    (net (code "376") (name "/RS232_RX") (class "Default")
      (node (ref "U1") (pin "B16") (pinfunction "IO,_LVDS78p,_DQ4T0/DQ5T9_B16") (pintype "bidirectional"))
    )
    (net (code "377") (name "/RS232_TX") (class "Default")
      (node (ref "U1") (pin "A14") (pinfunction "IO,_LVDS74n_A14") (pintype "bidirectional"))
    )
    (net (code "378") (name "/SCL") (class "Default")
      (node (ref "U1") (pin "Y11") (pinfunction "IO,_LVDS190n,_DQ3B2/DQ3B11_Y11") (pintype "bidirectional"))
    )
    (net (code "379") (name "/SDA") (class "Default")
      (node (ref "U1") (pin "AA10") (pinfunction "IO,_LVDS191p,_DQ3B5/DQ3B14_AA10") (pintype "bidirectional"))
    )
    (net (code "380") (name "/SPI_CLK") (class "Default")
      (node (ref "U1") (pin "F14") (pinfunction "IO,_LVDS75p,_DQ4T5/DQ5T14_F14") (pintype "bidirectional"))
    )
    (net (code "381") (name "/SPI_DIN") (class "Default")
      (node (ref "U1") (pin "F13") (pinfunction "IO,_LVDS76p_F13") (pintype "bidirectional"))
    )
    (net (code "382") (name "/SPI_DOUT") (class "Default")
      (node (ref "U1") (pin "F16") (pinfunction "IO,_LVDS83p,_DQ2T2/DQ5T2_F16") (pintype "bidirectional"))
    )
    (net (code "383") (name "/SPI_MODE") (class "Default")
      (node (ref "U1") (pin "F17") (pinfunction "IO,_LVDS86n_F17") (pintype "bidirectional"))
    )
    (net (code "384") (name "/SPI_SEL") (class "Default")
      (node (ref "U1") (pin "F15") (pinfunction "IO,_LVDS82n,_DQ2T3/DQ5T3_F15") (pintype "bidirectional"))
    )
    (net (code "385") (name "/SRAM1_A0") (class "Default")
      (node (ref "U1") (pin "AC18") (pinfunction "IO,_LVDS164n_AC18") (pintype "bidirectional"))
    )
    (net (code "386") (name "/SRAM1_A1") (class "Default")
      (node (ref "U1") (pin "AC19") (pinfunction "IO,_LVDS161n_AC19") (pintype "bidirectional"))
    )
    (net (code "387") (name "/SRAM1_A2") (class "Default")
      (node (ref "U1") (pin "AD21") (pinfunction "IO,_LVDS154n_AD21") (pintype "bidirectional"))
    )
    (net (code "388") (name "/SRAM1_A3") (class "Default")
      (node (ref "U1") (pin "AD22") (pinfunction "IO,_LVDS153n_AD22") (pintype "bidirectional"))
    )
    (net (code "389") (name "/SRAM1_A4") (class "Default")
      (node (ref "U1") (pin "AC22") (pinfunction "IO,_LVDS152p_AC22") (pintype "bidirectional"))
    )
    (net (code "390") (name "/SRAM1_A5") (class "Default")
      (node (ref "U1") (pin "U20") (pinfunction "IO,_LVDS136p_U20") (pintype "bidirectional"))
    )
    (net (code "391") (name "/SRAM1_A6") (class "Default")
      (node (ref "U1") (pin "T22") (pinfunction "IO,_LVDS129p,_DQ1R3/DQ3R3_T22") (pintype "bidirectional"))
    )
    (net (code "392") (name "/SRAM1_A7") (class "Default")
      (node (ref "U1") (pin "R24") (pinfunction "IO,_LVDS128n,_DQ1R1/DQ3R1_R24") (pintype "bidirectional"))
    )
    (net (code "393") (name "/SRAM1_A8") (class "Default")
      (node (ref "U1") (pin "P23") (pinfunction "IO,_LVDS127p,_(DPCLK6/DQS1R)/(DPCLK6/DQS1R)_P23") (pintype "bidirectional"))
    )
    (net (code "394") (name "/SRAM1_A9") (class "Default")
      (node (ref "U1") (pin "R20") (pinfunction "IO,_DQ1R2/DQ3R2_R20") (pintype "bidirectional"))
    )
    (net (code "395") (name "/SRAM1_A10") (class "Default")
      (node (ref "U1") (pin "V21") (pinfunction "IO,_PLL4_OUTp_V21") (pintype "bidirectional"))
    )
    (net (code "396") (name "/SRAM1_A11") (class "Default")
      (node (ref "U1") (pin "W19") (pinfunction "IO,_LVDS156n_W19") (pintype "bidirectional"))
    )
    (net (code "397") (name "/SRAM1_A12") (class "Default")
      (node (ref "U1") (pin "Y21") (pinfunction "IO_Y21") (pintype "bidirectional"))
    )
    (net (code "398") (name "/SRAM1_A13") (class "Default")
      (node (ref "U1") (pin "AA20") (pinfunction "IO,_DQ0B2/__AA20") (pintype "bidirectional"))
    )
    (net (code "399") (name "/SRAM1_A14") (class "Default")
      (node (ref "U1") (pin "U18") (pinfunction "IO,_LVDS157n_U18") (pintype "bidirectional"))
    )
    (net (code "400") (name "/SRAM1_A15") (class "Default")
      (node (ref "U1") (pin "AC17") (pinfunction "IO,_LVDS168p,_DQ2B4/DQ5B4_AC17") (pintype "bidirectional"))
    )
    (net (code "401") (name "/SRAM1_A16") (class "Default")
      (node (ref "U1") (pin "AD17") (pinfunction "IO,_LVDS168n,_DQ2B3/DQ5B3_AD17") (pintype "bidirectional"))
    )
    (net (code "402") (name "/SRAM1_A17") (class "Default")
      (node (ref "U1") (pin "AC16") (pinfunction "IO,_VREFB7N1_AC16") (pintype "bidirectional"))
    )
    (net (code "403") (name "/SRAM1_A18") (class "Default")
      (node (ref "U1") (pin "AA18") (pinfunction "IO,_LVDS162n_AA18") (pintype "bidirectional"))
    )
    (net (code "405") (name "/SRAM1_D0") (class "Default")
      (node (ref "U1") (pin "AA14") (pinfunction "IO,_LVDS174p_AA14") (pintype "bidirectional"))
    )
    (net (code "406") (name "/SRAM1_D1") (class "Default")
      (node (ref "U1") (pin "AA15") (pinfunction "IO,_LVDS173n,_DQ4B0/DQ5B9_AA15") (pintype "bidirectional"))
    )
    (net (code "407") (name "/SRAM1_D2") (class "Default")
      (node (ref "U1") (pin "AA16") (pinfunction "IO,_LVDS167p,_DQ2B2/DQ5B2_AA16") (pintype "bidirectional"))
    )
    (net (code "408") (name "/SRAM1_D3") (class "Default")
      (node (ref "U1") (pin "AA17") (pinfunction "IO,_LVDS162p_AA17") (pintype "bidirectional"))
    )
    (net (code "409") (name "/SRAM1_D4") (class "Default")
      (node (ref "U1") (pin "AE21") (pinfunction "IO,_LVDS158n_AE21") (pintype "bidirectional"))
    )
    (net (code "410") (name "/SRAM1_D5") (class "Default")
      (node (ref "U1") (pin "AB18") (pinfunction "IO,_LVDS164p_AB18") (pintype "bidirectional"))
    )
    (net (code "411") (name "/SRAM1_D6") (class "Default")
      (node (ref "U1") (pin "AB20") (pinfunction "IO,_LVDS159p,_DQ0B5/__AB20") (pintype "bidirectional"))
    )
    (net (code "412") (name "/SRAM1_D7") (class "Default")
      (node (ref "U1") (pin "AB21") (pinfunction "IO,_LVDS152n_AB21") (pintype "bidirectional"))
    )
    (net (code "413") (name "/SRAM1_D8") (class "Default")
      (node (ref "U1") (pin "Y18") (pinfunction "IO,_VREFB7N0_Y18") (pintype "bidirectional"))
    )
    (net (code "414") (name "/SRAM1_D9") (class "Default")
      (node (ref "U1") (pin "Y16") (pinfunction "IO,_LVDS167n,_DQ2B1/DQ5B1_Y16") (pintype "bidirectional"))
    )
    (net (code "415") (name "/SRAM1_D10") (class "Default")
      (node (ref "U1") (pin "Y15") (pinfunction "IO,_LVDS173p,_DQ4B1/DQ5B10_Y15") (pintype "bidirectional"))
    )
    (net (code "416") (name "/SRAM1_D11") (class "Default")
      (node (ref "U1") (pin "AD23") (pinfunction "IO,_LVDS153p_AD23") (pintype "bidirectional"))
    )
    (net (code "417") (name "/SRAM1_D12") (class "Default")
      (node (ref "U1") (pin "AC21") (pinfunction "IO,_LVDS154p,_(CDPCLK3/DQS0B)/(CDPCLK3/DQS0B)_AC21") (pintype "bidirectional"))
    )
    (net (code "418") (name "/SRAM1_D13") (class "Default")
      (node (ref "U1") (pin "AC20") (pinfunction "IO,_LVDS159n,_DQ0B4/__AC20") (pintype "bidirectional"))
    )
    (net (code "419") (name "/SRAM1_D14") (class "Default")
      (node (ref "U1") (pin "AD19") (pinfunction "IO,_LVDS161p,_DM0B/__AD19") (pintype "bidirectional"))
    )
    (net (code "420") (name "/SRAM1_D15") (class "Default")
      (node (ref "U1") (pin "AC15") (pinfunction "IO,_LVDS172n,_DM2B/(DM5B0/BWS#5B0)_AC15") (pintype "bidirectional"))
    )
    (net (code "421") (name "/SRAM1_NBHE") (class "Default")
      (node (ref "U1") (pin "AB15") (pinfunction "IO,_LVDS172p_AB15") (pintype "bidirectional"))
    )
    (net (code "422") (name "/SRAM1_NBLE") (class "Default")
      (node (ref "U1") (pin "AD15") (pinfunction "IO,_LVDS176n_AD15") (pintype "bidirectional"))
    )
    (net (code "423") (name "/SRAM1_NCS") (class "Default")
      (node (ref "U1") (pin "AC14") (pinfunction "IO,_DQ4B5/DQ5B14_AC14") (pintype "bidirectional"))
    )
    (net (code "424") (name "/SRAM1_NOE") (class "Default")
      (node (ref "U1") (pin "AD16") (pinfunction "IO,_LVDS171n,_DQ2B7/DQ5B7_AD16") (pintype "bidirectional"))
    )
    (net (code "425") (name "/SRAM1_NWE") (class "Default")
      (node (ref "U1") (pin "V20") (pinfunction "IO,_PLL4_OUTn_V20") (pintype "bidirectional"))
    )
    (net (code "427") (name "/SRAM2_A0") (class "Default")
      (node (ref "U1") (pin "W21") (pinfunction "IO,_LVDS148n_W21") (pintype "bidirectional"))
    )
    (net (code "428") (name "/SRAM2_A1") (class "Default")
      (node (ref "U1") (pin "V22") (pinfunction "IO,_VREFB6N1_V22") (pintype "bidirectional"))
    )
    (net (code "429") (name "/SRAM2_A2") (class "Default")
      (node (ref "U1") (pin "U22") (pinfunction "IO,_DQ3R7/DQ3R16_U22") (pintype "bidirectional"))
    )
    (net (code "430") (name "/SRAM2_A3") (class "Default")
      (node (ref "U1") (pin "P17") (pinfunction "IO,_LVDS130n_P17") (pintype "bidirectional"))
    )
    (net (code "431") (name "/SRAM2_A4") (class "Default")
      (node (ref "U1") (pin "AC23") (pinfunction "IO_AC23") (pintype "bidirectional"))
    )
    (net (code "432") (name "/SRAM2_A5") (class "Default")
      (node (ref "U1") (pin "U23") (pinfunction "IO,_LVDS134p,_(DM1R/BWS#1R)/(DM3R0/BWS#3R0)_U23") (pintype "bidirectional"))
    )
    (net (code "433") (name "/SRAM2_A6") (class "Default")
      (node (ref "U1") (pin "U24") (pinfunction "IO,_LVDS134n_U24") (pintype "bidirectional"))
    )
    (net (code "434") (name "/SRAM2_A7") (class "Default")
      (node (ref "U1") (pin "T23") (pinfunction "IO,_LVDS129n_T23") (pintype "bidirectional"))
    )
    (net (code "435") (name "/SRAM2_A8") (class "Default")
      (node (ref "U1") (pin "T24") (pinfunction "IO,_LVDS131p,_DQ1R4/DQ3R4_T24") (pintype "bidirectional"))
    )
    (net (code "436") (name "/SRAM2_A9") (class "Default")
      (node (ref "U1") (pin "P24") (pinfunction "IO,_LVDS127n_P24") (pintype "bidirectional"))
    )
    (net (code "437") (name "/SRAM2_A10") (class "Default")
      (node (ref "U1") (pin "R25") (pinfunction "IO,_LVDS128p,_DQ1R0/DQ3R0_R25") (pintype "bidirectional"))
    )
    (net (code "438") (name "/SRAM2_A11") (class "Default")
      (node (ref "U1") (pin "T25") (pinfunction "IO,_LVDS131n,_DQ1R5/DQ3R5_T25") (pintype "bidirectional"))
    )
    (net (code "439") (name "/SRAM2_A12") (class "Default")
      (node (ref "U1") (pin "U26") (pinfunction "IO,_LVDS133p,_DQ1R7/DQ3R7_U26") (pintype "bidirectional"))
    )
    (net (code "440") (name "/SRAM2_A13") (class "Default")
      (node (ref "U1") (pin "U25") (pinfunction "IO,_LVDS133n,_DQ1R8/DQ3R8_U25") (pintype "bidirectional"))
    )
    (net (code "441") (name "/SRAM2_A14") (class "Default")
      (node (ref "U1") (pin "V26") (pinfunction "IO,_LVDS137p,_DQ3R1/DQ3R10_V26") (pintype "bidirectional"))
    )
    (net (code "442") (name "/SRAM2_A15") (class "Default")
      (node (ref "U1") (pin "AE24") (pinfunction "IO,_LVDS150p_(nCEO)_AE24") (pintype "bidirectional"))
    )
    (net (code "443") (name "/SRAM2_A16") (class "Default")
      (node (ref "U1") (pin "AE23") (pinfunction "IO,_LVDS151n_AE23") (pintype "bidirectional"))
    )
    (net (code "444") (name "/SRAM2_A17") (class "Default")
      (node (ref "U1") (pin "AF23") (pinfunction "IO,_LVDS151p_AF23") (pintype "bidirectional"))
    )
    (net (code "445") (name "/SRAM2_A18") (class "Default")
      (node (ref "U1") (pin "V25") (pinfunction "IO,_LVDS137n,_DQ3R2/DQ3R11_V25") (pintype "bidirectional"))
    )
    (net (code "447") (name "/SRAM2_D0") (class "Default")
      (node (ref "U1") (pin "AB24") (pinfunction "IO,_LVDS146n_AB24") (pintype "bidirectional"))
    )
    (net (code "448") (name "/SRAM2_D1") (class "Default")
      (node (ref "U1") (pin "AA23") (pinfunction "IO,_LVDS147p_AA23") (pintype "bidirectional"))
    )
    (net (code "449") (name "/SRAM2_D2") (class "Default")
      (node (ref "U1") (pin "AA24") (pinfunction "IO,_LVDS147n_AA24") (pintype "bidirectional"))
    )
    (net (code "450") (name "/SRAM2_D3") (class "Default")
      (node (ref "U1") (pin "Y23") (pinfunction "IO,_LVDS143p_Y23") (pintype "bidirectional"))
    )
    (net (code "451") (name "/SRAM2_D4") (class "Default")
      (node (ref "U1") (pin "Y24") (pinfunction "IO,_LVDS143n_Y24") (pintype "bidirectional"))
    )
    (net (code "452") (name "/SRAM2_D5") (class "Default")
      (node (ref "U1") (pin "W23") (pinfunction "IO,_LVDS140p,_DQ3R5/DQ3R14_W23") (pintype "bidirectional"))
    )
    (net (code "453") (name "/SRAM2_D6") (class "Default")
      (node (ref "U1") (pin "W24") (pinfunction "IO,_LVDS140n,_DQ3R6/DQ3R15_W24") (pintype "bidirectional"))
    )
    (net (code "454") (name "/SRAM2_D7") (class "Default")
      (node (ref "U1") (pin "V23") (pinfunction "IO,_LVDS138n,_DQ3R4/DQ3R13_V23") (pintype "bidirectional"))
    )
    (net (code "455") (name "/SRAM2_D8") (class "Default")
      (node (ref "U1") (pin "W26") (pinfunction "IO,_LVDS139p,_(CDPCLK4/DQS3R)/(CDPCLK4/DQS3R)_W26") (pintype "bidirectional"))
    )
    (net (code "456") (name "/SRAM2_D9") (class "Default")
      (node (ref "U1") (pin "W25") (pinfunction "IO,_LVDS139n_W25") (pintype "bidirectional"))
    )
    (net (code "457") (name "/SRAM2_D10") (class "Default")
      (node (ref "U1") (pin "Y26") (pinfunction "IO,_LVDS141n,_(DM3R/BWS#3R)/(DM3R1/BWS#3R1)_Y26") (pintype "bidirectional"))
    )
    (net (code "458") (name "/SRAM2_D11") (class "Default")
      (node (ref "U1") (pin "Y25") (pinfunction "IO,_LVDS141p,_DQ3R8/DQ3R17_Y25") (pintype "bidirectional"))
    )
    (net (code "459") (name "/SRAM2_D12") (class "Default")
      (node (ref "U1") (pin "AA26") (pinfunction "IO,_LVDS142p_AA26") (pintype "bidirectional"))
    )
    (net (code "460") (name "/SRAM2_D13") (class "Default")
      (node (ref "U1") (pin "AA25") (pinfunction "IO,_LVDS142n_AA25") (pintype "bidirectional"))
    )
    (net (code "461") (name "/SRAM2_D14") (class "Default")
      (node (ref "U1") (pin "AB26") (pinfunction "IO,_LVDS144n_AB26") (pintype "bidirectional"))
    )
    (net (code "462") (name "/SRAM2_D15") (class "Default")
      (node (ref "U1") (pin "AB25") (pinfunction "IO,_LVDS144p_AB25") (pintype "bidirectional"))
    )
    (net (code "463") (name "/SRAM2_NBHE") (class "Default")
      (node (ref "U1") (pin "AC25") (pinfunction "IO,_LVDS145n_AC25") (pintype "bidirectional"))
    )
    (net (code "464") (name "/SRAM2_NBLE") (class "Default")
      (node (ref "U1") (pin "AC26") (pinfunction "IO,_LVDS145p_AC26") (pintype "bidirectional"))
    )
    (net (code "465") (name "/SRAM2_NCS") (class "Default")
      (node (ref "U1") (pin "AD24") (pinfunction "IO,_LVDS149p_AD24") (pintype "bidirectional"))
    )
    (net (code "466") (name "/SRAM2_NOE") (class "Default")
      (node (ref "U1") (pin "AD25") (pinfunction "IO,_LVDS149n_AD25") (pintype "bidirectional"))
    )
    (net (code "467") (name "/SRAM2_NWE") (class "Default")
      (node (ref "U1") (pin "V24") (pinfunction "IO,_LVDS138p,_DQ3R3/DQ3R12_V24") (pintype "bidirectional"))
    )
    (net (code "469") (name "/STATUS_LED") (class "Default")
      (node (ref "NT6") (pin "1") (pinfunction "Net1_1") (pintype "passive"))
    )
    (net (code "470") (name "/SW0") (class "Default")
      (node (ref "U1") (pin "AA11") (pinfunction "IO,_LVDS190p,_DQ3B3/DQ3B12_AA11") (pintype "bidirectional"))
    )
    (net (code "471") (name "/SW1") (class "Default")
      (node (ref "U1") (pin "AB10") (pinfunction "IO,_LVDS191n,_DQ3B4/DQ3B13_AB10") (pintype "bidirectional"))
    )
    (net (code "472") (name "/SW2") (class "Default")
      (node (ref "U1") (pin "Y10") (pinfunction "IO,_LVDS194n,_DQ1B2/__Y10") (pintype "bidirectional"))
    )
    (net (code "473") (name "/SW3") (class "Default")
      (node (ref "U1") (pin "AB8") (pinfunction "IO,_DQ1B1/__AB8") (pintype "bidirectional"))
    )
    (net (code "474") (name "/SW4") (class "Default")
      (node (ref "U1") (pin "AA7") (pinfunction "IO,_PLL1_OUTp_AA7") (pintype "bidirectional"))
    )
    (net (code "476") (name "/TCK") (class "Default")
      (node (ref "R14") (pin "2") (pinfunction "2_2") (pintype "passive"))
    )
    (net (code "477") (name "/TDI") (class "Default")
      (node (ref "R20") (pin "2") (pinfunction "2_2") (pintype "passive"))
    )
    (net (code "478") (name "/TDO") (class "Default")
      (node (ref "R22") (pin "2") (pinfunction "2_2") (pintype "passive"))
    )
    (net (code "480") (name "/TMS") (class "Default")
      (node (ref "R12") (pin "2") (pinfunction "2_2") (pintype "passive"))
    )
    (net (code "483") (name "/nCONFIG") (class "Default")
      (node (ref "R24") (pin "2") (pinfunction "2_2") (pintype "passive"))
    )
    (net (code "484") (name "/nSTATUS") (class "Default")
      (node (ref "R8") (pin "2") (pinfunction "2_2") (pintype "passive"))
    )
    (net (code "504") (name "3V3") (class "Default")
      (node (ref "NT2") (pin "2") (pinfunction "Net2_2") (pintype "passive"))
      (node (ref "R1") (pin "2") (pinfunction "2_2") (pintype "passive"))
      (node (ref "R2") (pin "2") (pinfunction "2_2") (pintype "passive"))
      (node (ref "R3") (pin "2") (pinfunction "2_2") (pintype "passive"))
      (node (ref "R4") (pin "2") (pinfunction "2_2") (pintype "passive"))
      (node (ref "R7") (pin "2") (pinfunction "2_2") (pintype "passive"))
    )
    (net (code "505") (name "GND") (class "Default")
      (node (ref "NT3") (pin "2") (pinfunction "Net2_2") (pintype "passive"))
      (node (ref "NT4") (pin "2") (pinfunction "Net2_2") (pintype "passive"))
      (node (ref "NT5") (pin "2") (pinfunction "Net2_2") (pintype "passive"))
      (node (ref "U1") (pin "A13") (pinfunction "CLK9,_LVDSCLK4p_INPUT_A13") (pintype "input"))
      (node (ref "U1") (pin "AD13") (pinfunction "CLK14,_LVDSCLK7n_INPUT_AD13") (pintype "input"))
      (node (ref "U1") (pin "AE14") (pinfunction "CLK12,_LVDSCLK6n_INPUT_AE14") (pintype "input"))
      (node (ref "U1") (pin "D13") (pinfunction "CLK11,_LVDSCLK5p_INPUT_D13") (pintype "input"))
      (node (ref "U1") (pin "N1") (pinfunction "CLK1,_LVDSCLK0n_INPUT_N1") (pintype "input"))
      (node (ref "U1") (pin "N2") (pinfunction "CLK0,_LVDSCLK0p_INPUT_N2") (pintype "input"))
      (node (ref "U1") (pin "N25") (pinfunction "CLK4,_LVDSCLK2p_INPUT_N25") (pintype "input"))
      (node (ref "U1") (pin "N26") (pinfunction "CLK5,_LVDSCLK2n_INPUT_N26") (pintype "input"))
      (node (ref "U1") (pin "P1") (pinfunction "CLK3,_LVDSCLK1n_INPUT_P1") (pintype "input"))
      (node (ref "U1") (pin "P2") (pinfunction "CLK2,_LVDSCLK1p_INPUT_P2") (pintype "input"))
      (node (ref "U1") (pin "P25") (pinfunction "CLK6,_LVDSCLK3p_INPUT_P25") (pintype "input"))
      (node (ref "U1") (pin "P26") (pinfunction "CLK7,_LVDSCLK3n_INPUT_P26") (pintype "input"))
    )
    (net (code "506") (name "unconnected-(U1A-IO,_LVDS0n-PadAB4)") (class "Default")
      (node (ref "U1") (pin "AB4") (pinfunction "IO,_LVDS0n_AB4") (pintype "bidirectional"))
    )
    (net (code "507") (name "unconnected-(U1A-IO,_LVDS0p-PadAB3)") (class "Default")
      (node (ref "U1") (pin "AB3") (pinfunction "IO,_LVDS0p_AB3") (pintype "bidirectional"))
    )
    (net (code "508") (name "unconnected-(U1A-IO,_LVDS2n-PadAD3)") (class "Default")
      (node (ref "U1") (pin "AD3") (pinfunction "IO,_LVDS2n_AD3") (pintype "bidirectional"))
    )
    (net (code "509") (name "unconnected-(U1A-IO,_LVDS5n-PadAA3)") (class "Default")
      (node (ref "U1") (pin "AA3") (pinfunction "IO,_LVDS5n_AA3") (pintype "bidirectional"))
    )
    (net (code "510") (name "unconnected-(U1A-IO,_LVDS5p-PadAA4)") (class "Default")
      (node (ref "U1") (pin "AA4") (pinfunction "IO,_LVDS5p_AA4") (pintype "bidirectional"))
    )
    (net (code "511") (name "unconnected-(U1A-IO,_LVDS8n-PadY4)") (class "Default")
      (node (ref "U1") (pin "Y4") (pinfunction "IO,_LVDS8n_Y4") (pintype "bidirectional"))
    )
    (net (code "512") (name "unconnected-(U1A-IO,_LVDS8p-PadY3)") (class "Default")
      (node (ref "U1") (pin "Y3") (pinfunction "IO,_LVDS8p_Y3") (pintype "bidirectional"))
    )
    (net (code "513") (name "unconnected-(U1A-IO,_LVDS11p,_(CDPCLK1{slash}DQS3L){slash}(CDPCLK1{slash}DQS3L)-PadW4)") (class "Default")
      (node (ref "U1") (pin "W4") (pinfunction "IO,_LVDS11p,_(CDPCLK1/DQS3L)/(CDPCLK1/DQS3L)_W4") (pintype "bidirectional"))
    )
    (net (code "514") (name "unconnected-(U1A-IO,_LVDS12n,_DQ3L3{slash}DQ3L12-PadU7)") (class "Default")
      (node (ref "U1") (pin "U7") (pinfunction "IO,_LVDS12n,_DQ3L3/DQ3L12_U7") (pintype "bidirectional"))
    )
    (net (code "515") (name "unconnected-(U1A-IO,_LVDS14n-PadV3)") (class "Default")
      (node (ref "U1") (pin "V3") (pinfunction "IO,_LVDS14n_V3") (pintype "bidirectional"))
    )
    (net (code "516") (name "unconnected-(U1A-IO,_LVDS15p-PadT7)") (class "Default")
      (node (ref "U1") (pin "T7") (pinfunction "IO,_LVDS15p_T7") (pintype "bidirectional"))
    )
    (net (code "517") (name "unconnected-(U1A-IO,_LVDS18n-PadU10)") (class "Default")
      (node (ref "U1") (pin "U10") (pinfunction "IO,_LVDS18n_U10") (pintype "bidirectional"))
    )
    (net (code "518") (name "unconnected-(U1A-IO,_LVDS23p-PadT10)") (class "Default")
      (node (ref "U1") (pin "T10") (pinfunction "IO,_LVDS23p_T10") (pintype "bidirectional"))
    )
    (net (code "519") (name "unconnected-(U1A-IO-PadAC3)") (class "Default")
      (node (ref "U1") (pin "AC3") (pinfunction "IO_AC3") (pintype "bidirectional"))
    )
    (net (code "520") (name "unconnected-(U1B-IO,_(nCSO)-PadD3)") (class "Default")
      (node (ref "U1") (pin "D3") (pinfunction "IO,_(nCSO)_D3") (pintype "bidirectional"))
    )
    (net (code "521") (name "unconnected-(U1B-IO,_LVDS44n-PadJ7)") (class "Default")
      (node (ref "U1") (pin "J7") (pinfunction "IO,_LVDS44n_J7") (pintype "bidirectional"))
    )
    (net (code "522") (name "unconnected-(U1B-IO,_LVDS46n-PadF4)") (class "Default")
      (node (ref "U1") (pin "F4") (pinfunction "IO,_LVDS46n_F4") (pintype "bidirectional"))
    )
    (net (code "523") (name "unconnected-(U1B-IO,_LVDS49p_(CRC_ERROR)-PadB2)") (class "Default")
      (node (ref "U1") (pin "B2") (pinfunction "IO,_LVDS49p_(CRC_ERROR)_B2") (pintype "bidirectional"))
    )
    (net (code "524") (name "unconnected-(U1B-IO,_PLL3_OUTn-PadF6)") (class "Default")
      (node (ref "U1") (pin "F6") (pinfunction "IO,_PLL3_OUTn_F6") (pintype "bidirectional"))
    )
    (net (code "525") (name "unconnected-(U1B-IO,_PLL3_OUTp-PadE5)") (class "Default")
      (node (ref "U1") (pin "E5") (pinfunction "IO,_PLL3_OUTp_E5") (pintype "bidirectional"))
    )
    (net (code "526") (name "unconnected-(U1C-IO,_LVDS55n-PadJ9)") (class "Default")
      (node (ref "U1") (pin "J9") (pinfunction "IO,_LVDS55n_J9") (pintype "bidirectional"))
    )
    (net (code "527") (name "unconnected-(U1C-IO,_LVDS56p-PadH10)") (class "Default")
      (node (ref "U1") (pin "H10") (pinfunction "IO,_LVDS56p_H10") (pintype "bidirectional"))
    )
    (net (code "528") (name "unconnected-(U1C-IO,_LVDS59n,_DQ3T5{slash}DQ3T14-PadC8)") (class "Default")
      (node (ref "U1") (pin "C8") (pinfunction "IO,_LVDS59n,_DQ3T5/DQ3T14_C8") (pintype "bidirectional"))
    )
    (net (code "529") (name "unconnected-(U1C-IO,_LVDS68n,_DQ5T1{slash}DQ3T1-PadD12)") (class "Default")
      (node (ref "U1") (pin "D12") (pinfunction "IO,_LVDS68n,_DQ5T1/DQ3T1_D12") (pintype "bidirectional"))
    )
    (net (code "530") (name "unconnected-(U1C-IO,_LVDS71p-PadJ10)") (class "Default")
      (node (ref "U1") (pin "J10") (pinfunction "IO,_LVDS71p_J10") (pintype "bidirectional"))
    )
    (net (code "531") (name "unconnected-(U1C-IO,_LVDS73n-PadB12)") (class "Default")
      (node (ref "U1") (pin "B12") (pinfunction "IO,_LVDS73n_B12") (pintype "bidirectional"))
    )
    (net (code "532") (name "unconnected-(U1D-IO,_LVDS74p,_(DPCLK9{slash}DQS4T){slash}(DPCLK9{slash}DQS4T)-PadB14)") (class "Default")
      (node (ref "U1") (pin "B14") (pinfunction "IO,_LVDS74p,_(DPCLK9/DQS4T)/(DPCLK9/DQS4T)_B14") (pintype "bidirectional"))
    )
    (net (code "533") (name "unconnected-(U1D-IO,_LVDS80n-PadH16)") (class "Default")
      (node (ref "U1") (pin "H16") (pinfunction "IO,_LVDS80n_H16") (pintype "bidirectional"))
    )
    (net (code "534") (name "unconnected-(U1D-IO,_LVDS80p-PadH15)") (class "Default")
      (node (ref "U1") (pin "H15") (pinfunction "IO,_LVDS80p_H15") (pintype "bidirectional"))
    )
    (net (code "535") (name "unconnected-(U1D-IO,_LVDS89p,_DM0T{slash}_-PadD18)") (class "Default")
      (node (ref "U1") (pin "D18") (pinfunction "IO,_LVDS89p,_DM0T/__D18") (pintype "bidirectional"))
    )
    (net (code "536") (name "unconnected-(U1D-IO,_LVDS90p,_DQ0T7{slash}_-PadA19)") (class "Default")
      (node (ref "U1") (pin "A19") (pinfunction "IO,_LVDS90p,_DQ0T7/__A19") (pintype "bidirectional"))
    )
    (net (code "537") (name "unconnected-(U1D-IO,_LVDS91n,_DQ0T4{slash}_-PadC19)") (class "Default")
      (node (ref "U1") (pin "C19") (pinfunction "IO,_LVDS91n,_DQ0T4/__C19") (pintype "bidirectional"))
    )
    (net (code "538") (name "unconnected-(U1D-IO,_LVDS93p-PadK16)") (class "Default")
      (node (ref "U1") (pin "K16") (pinfunction "IO,_LVDS93p_K16") (pintype "bidirectional"))
    )
    (net (code "539") (name "unconnected-(U1D-IO,_LVDS94p-PadK17)") (class "Default")
      (node (ref "U1") (pin "K17") (pinfunction "IO,_LVDS94p_K17") (pintype "bidirectional"))
    )
    (net (code "540") (name "unconnected-(U1D-IO,_LVDS98n-PadC21)") (class "Default")
      (node (ref "U1") (pin "C21") (pinfunction "IO,_LVDS98n_C21") (pintype "bidirectional"))
    )
    (net (code "541") (name "unconnected-(U1E-IO,_LVDS103n-PadB25)") (class "Default")
      (node (ref "U1") (pin "B25") (pinfunction "IO,_LVDS103n_B25") (pintype "bidirectional"))
    )
    (net (code "542") (name "unconnected-(U1E-IO,_LVDS107p-PadF24)") (class "Default")
      (node (ref "U1") (pin "F24") (pinfunction "IO,_LVDS107p_F24") (pintype "bidirectional"))
    )
    (net (code "543") (name "unconnected-(U1E-IO,_LVDS110p-PadN18)") (class "Default")
      (node (ref "U1") (pin "N18") (pinfunction "IO,_LVDS110p_N18") (pintype "bidirectional+no_connect"))
    )
    (net (code "544") (name "unconnected-(U1E-IO,_LVDS111n-PadG24)") (class "Default")
      (node (ref "U1") (pin "G24") (pinfunction "IO,_LVDS111n_G24") (pintype "bidirectional"))
    )
    (net (code "545") (name "unconnected-(U1E-IO,_LVDS111p-PadG23)") (class "Default")
      (node (ref "U1") (pin "G23") (pinfunction "IO,_LVDS111p_G23") (pintype "bidirectional"))
    )
    (net (code "546") (name "unconnected-(U1E-IO,_LVDS116n,_DQ2R6{slash}DQ1R6-PadK19)") (class "Default")
      (node (ref "U1") (pin "K19") (pinfunction "IO,_LVDS116n,_DQ2R6/DQ1R6_K19") (pintype "bidirectional+no_connect"))
    )
    (net (code "547") (name "unconnected-(U1E-IO,_LVDS116p-PadK18)") (class "Default")
      (node (ref "U1") (pin "K18") (pinfunction "IO,_LVDS116p_K18") (pintype "bidirectional+no_connect"))
    )
    (net (code "548") (name "unconnected-(U1E-IO,_LVDS120p-PadL24)") (class "Default")
      (node (ref "U1") (pin "L24") (pinfunction "IO,_LVDS120p_L24") (pintype "bidirectional"))
    )
    (net (code "549") (name "unconnected-(U1E-IO,_LVDS121n,_DQ0R2{slash}DQ1R11-PadK26)") (class "Default")
      (node (ref "U1") (pin "K26") (pinfunction "IO,_LVDS121n,_DQ0R2/DQ1R11_K26") (pintype "bidirectional"))
    )
    (net (code "550") (name "unconnected-(U1E-IO,_LVDS122p,_DQ0R3{slash}DQ1R12-PadM22)") (class "Default")
      (node (ref "U1") (pin "M22") (pinfunction "IO,_LVDS122p,_DQ0R3/DQ1R12_M22") (pintype "bidirectional"))
    )
    (net (code "551") (name "unconnected-(U1E-IO,_LVDS124p,_DQ0R7{slash}DQ1R16-PadN20)") (class "Default")
      (node (ref "U1") (pin "N20") (pinfunction "IO,_LVDS124p,_DQ0R7/DQ1R16_N20") (pintype "bidirectional"))
    )
    (net (code "552") (name "unconnected-(U1E-IO,_LVDS125n,_DM0R{slash}(DM1R1{slash}BWS#1R1)-PadM25)") (class "Default")
      (node (ref "U1") (pin "M25") (pinfunction "IO,_LVDS125n,_DM0R/(DM1R1/BWS#1R1)_M25") (pintype "bidirectional"))
    )
    (net (code "553") (name "unconnected-(U1E-IO,_LVDS126n-PadN24)") (class "Default")
      (node (ref "U1") (pin "N24") (pinfunction "IO,_LVDS126n_N24") (pintype "bidirectional"))
    )
    (net (code "554") (name "unconnected-(U1F-IO,_LVDS148p-PadY22)") (class "Default")
      (node (ref "U1") (pin "Y22") (pinfunction "IO,_LVDS148p_Y22") (pintype "bidirectional+no_connect"))
    )
    (net (code "555") (name "unconnected-(U1H-IO,_LVDS177p,_(DPCLK3{slash}DQS5B){slash}(DPCLK3{slash}DQS5B)-PadAE13)") (class "Default")
      (node (ref "U1") (pin "AE13") (pinfunction "IO,_LVDS177p,_(DPCLK3/DQS5B)/(DPCLK3/DQS5B)_AE13") (pintype "bidirectional"))
    )
  )
)
